# CPU_Logic.net
KiCad netlist of a schematic drawn in Altium Designer
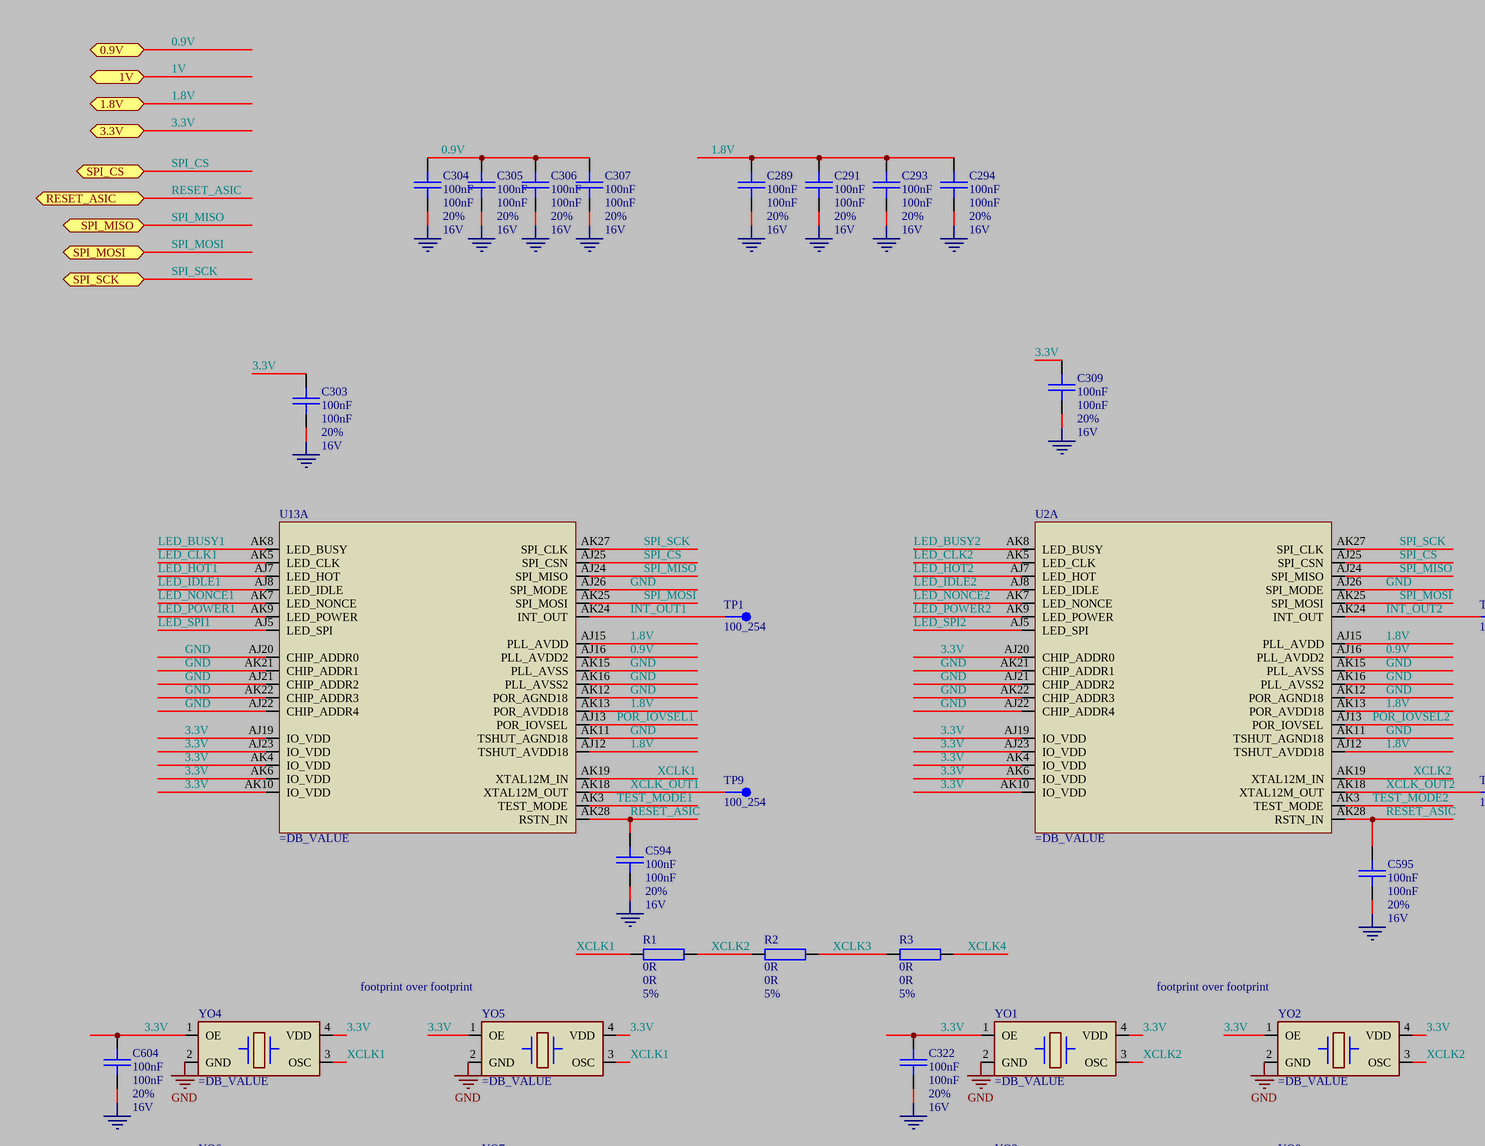
[diagram p0: CPU_Logic.SchDoc, top left]
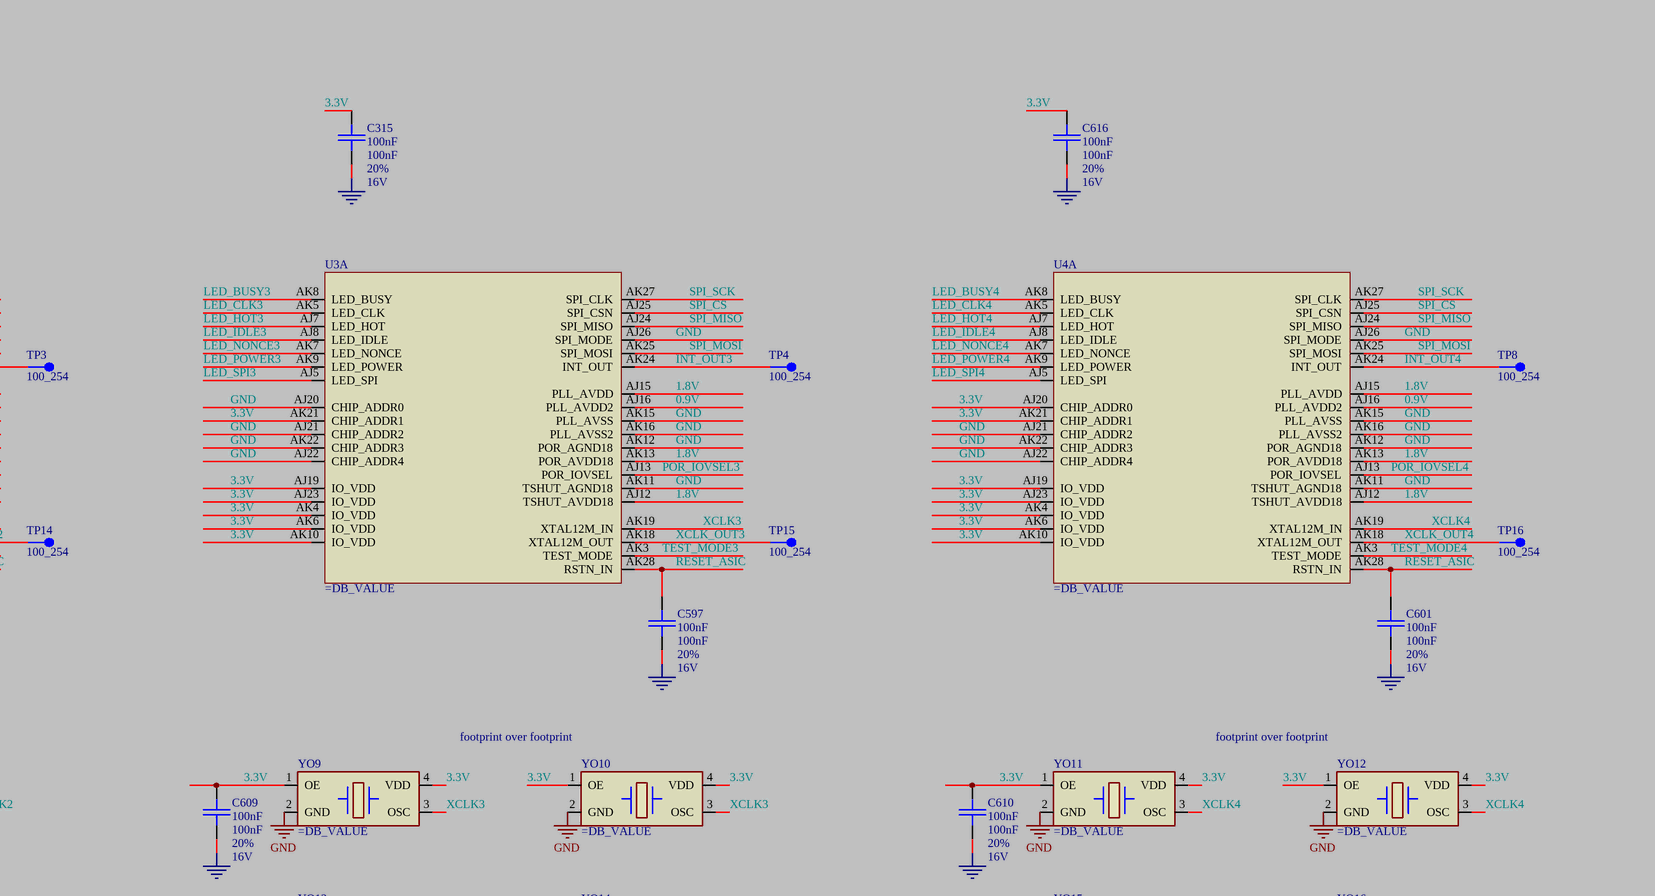
[diagram p1: CPU_Logic.SchDoc, top right]
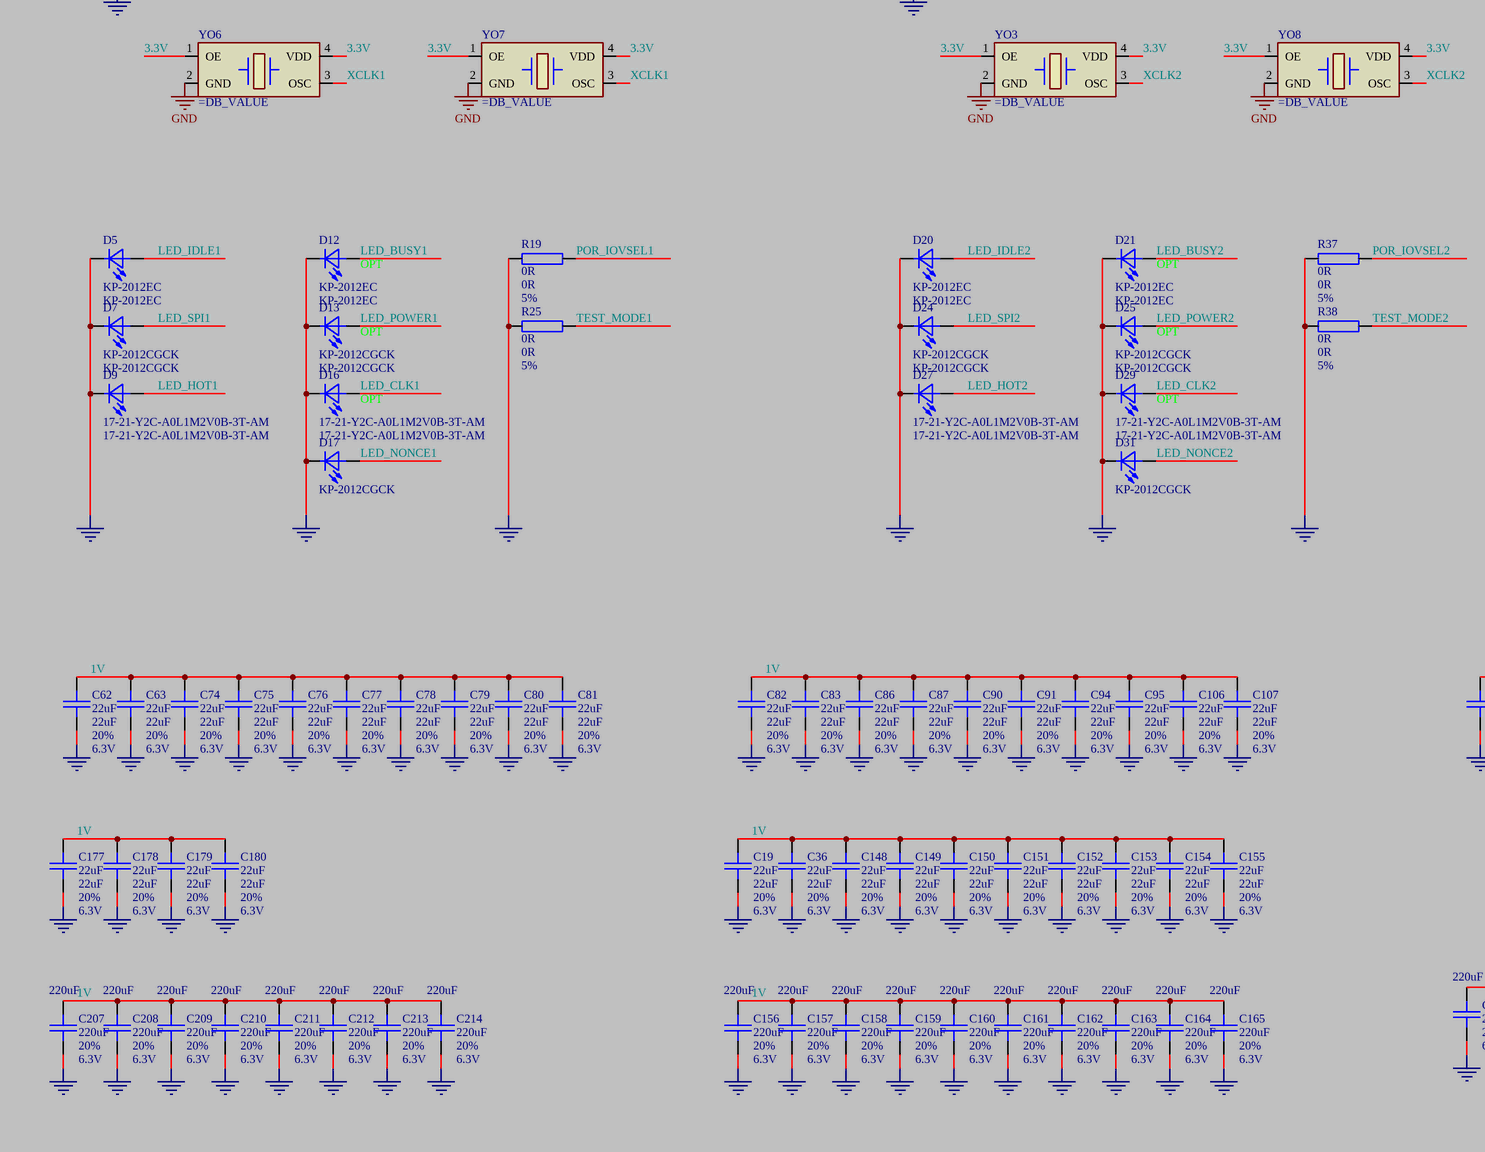
[diagram p2: CPU_Logic.SchDoc, bottom left]
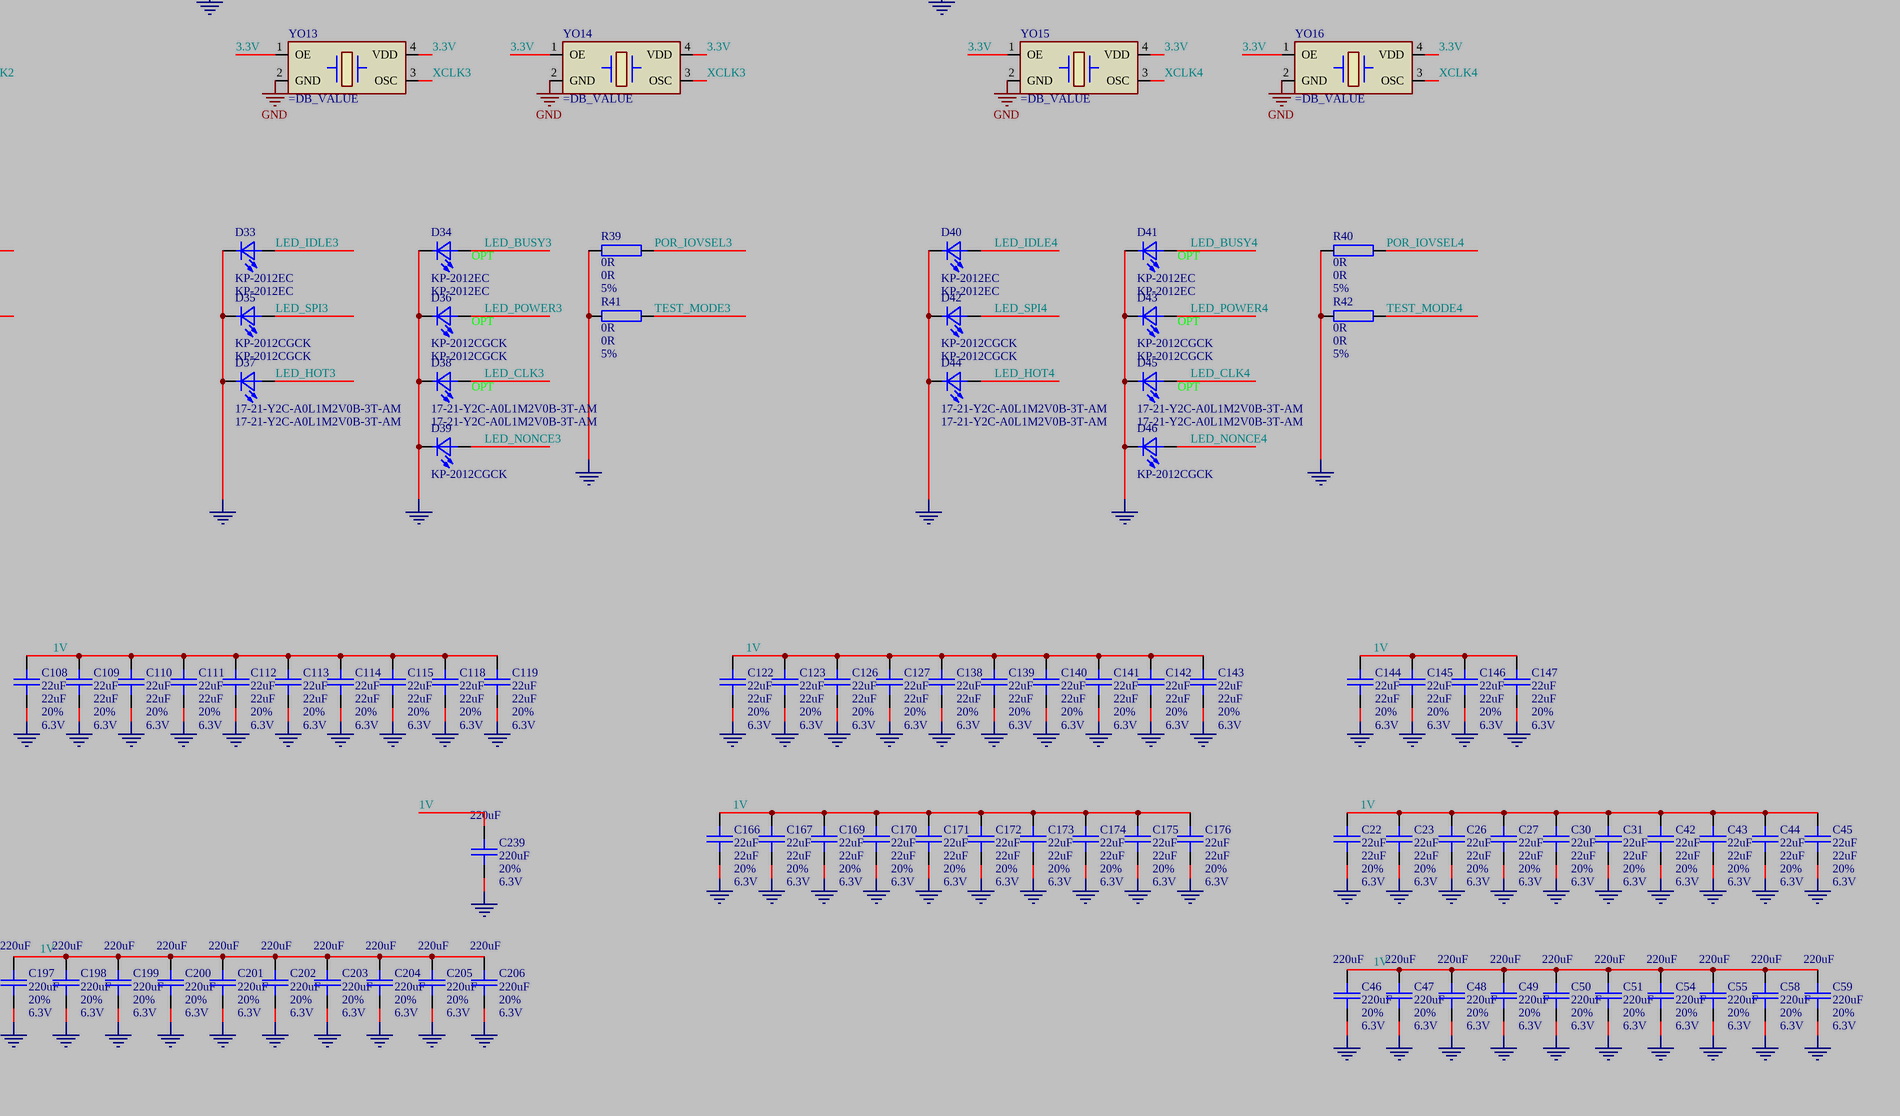
[diagram p3: CPU_Logic.SchDoc, bottom right]

(export (version "E")
  (design (tool "Eeschema 10.0.6"))
  (components
    (comp (ref "C19")
      (value "22uF")
      (footprint "SMD_0805_CAPC2012X145N")
      (fields
        (field (name "DB_PART_NUMBER") "CAP000043686")
        (field (name "DB_VALUE") "22uF")
        (field (name "DB_TOLERANCE") "20%")
        (field (name "DB_VOLTAGE") "6.3V")
        (field (name "DB_MANUFACTURER_PART") "KEMET    C0805C226M9PAC")
        (field (name "DB_APPROVED_BY") "ISHIDDEN=T")
      )
      (libsource (lib "Database_Libs1") (part "C"))
    )
    (comp (ref "C22")
      (value "22uF")
      (footprint "SMD_0805_CAPC2012X145N")
      (fields
        (field (name "DB_PART_NUMBER") "CAP000043686")
        (field (name "DB_VALUE") "22uF")
        (field (name "DB_TOLERANCE") "20%")
        (field (name "DB_VOLTAGE") "6.3V")
        (field (name "DB_MANUFACTURER_PART") "KEMET    C0805C226M9PAC")
        (field (name "DB_APPROVED_BY") "ISHIDDEN=T")
      )
      (libsource (lib "Database_Libs1") (part "C"))
    )
    (comp (ref "C23")
      (value "22uF")
      (footprint "SMD_0805_CAPC2012X145N")
      (fields
        (field (name "DB_PART_NUMBER") "CAP000043686")
        (field (name "DB_VALUE") "22uF")
        (field (name "DB_TOLERANCE") "20%")
        (field (name "DB_VOLTAGE") "6.3V")
        (field (name "DB_MANUFACTURER_PART") "KEMET    C0805C226M9PAC")
        (field (name "DB_APPROVED_BY") "ISHIDDEN=T")
      )
      (libsource (lib "Database_Libs1") (part "C"))
    )
    (comp (ref "C26")
      (value "22uF")
      (footprint "SMD_0805_CAPC2012X145N")
      (fields
        (field (name "DB_PART_NUMBER") "CAP000043686")
        (field (name "DB_VALUE") "22uF")
        (field (name "DB_TOLERANCE") "20%")
        (field (name "DB_VOLTAGE") "6.3V")
        (field (name "DB_MANUFACTURER_PART") "KEMET    C0805C226M9PAC")
        (field (name "DB_APPROVED_BY") "ISHIDDEN=T")
      )
      (libsource (lib "Database_Libs1") (part "C"))
    )
    (comp (ref "C27")
      (value "22uF")
      (footprint "SMD_0805_CAPC2012X145N")
      (fields
        (field (name "DB_PART_NUMBER") "CAP000043686")
        (field (name "DB_VALUE") "22uF")
        (field (name "DB_TOLERANCE") "20%")
        (field (name "DB_VOLTAGE") "6.3V")
        (field (name "DB_MANUFACTURER_PART") "KEMET    C0805C226M9PAC")
        (field (name "DB_APPROVED_BY") "ISHIDDEN=T")
      )
      (libsource (lib "Database_Libs1") (part "C"))
    )
    (comp (ref "C30")
      (value "22uF")
      (footprint "SMD_0805_CAPC2012X145N")
      (fields
        (field (name "DB_PART_NUMBER") "CAP000043686")
        (field (name "DB_VALUE") "22uF")
        (field (name "DB_TOLERANCE") "20%")
        (field (name "DB_VOLTAGE") "6.3V")
        (field (name "DB_MANUFACTURER_PART") "KEMET    C0805C226M9PAC")
        (field (name "DB_APPROVED_BY") "ISHIDDEN=T")
      )
      (libsource (lib "Database_Libs1") (part "C"))
    )
    (comp (ref "C31")
      (value "22uF")
      (footprint "SMD_0805_CAPC2012X145N")
      (fields
        (field (name "DB_PART_NUMBER") "CAP000043686")
        (field (name "DB_VALUE") "22uF")
        (field (name "DB_TOLERANCE") "20%")
        (field (name "DB_VOLTAGE") "6.3V")
        (field (name "DB_MANUFACTURER_PART") "KEMET    C0805C226M9PAC")
        (field (name "DB_APPROVED_BY") "ISHIDDEN=T")
      )
      (libsource (lib "Database_Libs1") (part "C"))
    )
    (comp (ref "C36")
      (value "22uF")
      (footprint "SMD_0805_CAPC2012X145N")
      (fields
        (field (name "DB_PART_NUMBER") "CAP000043686")
        (field (name "DB_VALUE") "22uF")
        (field (name "DB_TOLERANCE") "20%")
        (field (name "DB_VOLTAGE") "6.3V")
        (field (name "DB_MANUFACTURER_PART") "KEMET    C0805C226M9PAC")
        (field (name "DB_APPROVED_BY") "ISHIDDEN=T")
      )
      (libsource (lib "Database_Libs1") (part "C"))
    )
    (comp (ref "C42")
      (value "22uF")
      (footprint "SMD_0805_CAPC2012X145N")
      (fields
        (field (name "DB_PART_NUMBER") "CAP000043686")
        (field (name "DB_VALUE") "22uF")
        (field (name "DB_TOLERANCE") "20%")
        (field (name "DB_VOLTAGE") "6.3V")
        (field (name "DB_MANUFACTURER_PART") "KEMET    C0805C226M9PAC")
        (field (name "DB_APPROVED_BY") "ISHIDDEN=T")
      )
      (libsource (lib "Database_Libs1") (part "C"))
    )
    (comp (ref "C43")
      (value "22uF")
      (footprint "SMD_0805_CAPC2012X145N")
      (fields
        (field (name "DB_PART_NUMBER") "CAP000043686")
        (field (name "DB_VALUE") "22uF")
        (field (name "DB_TOLERANCE") "20%")
        (field (name "DB_VOLTAGE") "6.3V")
        (field (name "DB_MANUFACTURER_PART") "KEMET    C0805C226M9PAC")
        (field (name "DB_APPROVED_BY") "ISHIDDEN=T")
      )
      (libsource (lib "Database_Libs1") (part "C"))
    )
    (comp (ref "C44")
      (value "22uF")
      (footprint "SMD_0805_CAPC2012X145N")
      (fields
        (field (name "DB_PART_NUMBER") "CAP000043686")
        (field (name "DB_VALUE") "22uF")
        (field (name "DB_TOLERANCE") "20%")
        (field (name "DB_VOLTAGE") "6.3V")
        (field (name "DB_MANUFACTURER_PART") "KEMET    C0805C226M9PAC")
        (field (name "DB_APPROVED_BY") "ISHIDDEN=T")
      )
      (libsource (lib "Database_Libs1") (part "C"))
    )
    (comp (ref "C45")
      (value "22uF")
      (footprint "SMD_0805_CAPC2012X145N")
      (fields
        (field (name "DB_PART_NUMBER") "CAP000043686")
        (field (name "DB_VALUE") "22uF")
        (field (name "DB_TOLERANCE") "20%")
        (field (name "DB_VOLTAGE") "6.3V")
        (field (name "DB_MANUFACTURER_PART") "KEMET    C0805C226M9PAC")
        (field (name "DB_APPROVED_BY") "ISHIDDEN=T")
      )
      (libsource (lib "Database_Libs1") (part "C"))
    )
    (comp (ref "C46")
      (value "220uF")
      (footprint "SMD_1210_CAPC3225X279N")
      (fields
        (field (name "DB_PART_NUMBER") "CAP000047355")
        (field (name "DB_VALUE") "220uF")
        (field (name "DB_TOLERANCE") "20%")
        (field (name "DB_VOLTAGE") "6.3V")
        (field (name "DB_MANUFACTURER_PART") "SAMSUNG    CL32A227MQVNNNE")
        (field (name "DB_APPROVED_BY") "VSN")
      )
      (libsource (lib "Database_Libs1") (part "C"))
    )
    (comp (ref "C47")
      (value "220uF")
      (footprint "SMD_1210_CAPC3225X279N")
      (fields
        (field (name "DB_PART_NUMBER") "CAP000047355")
        (field (name "DB_VALUE") "220uF")
        (field (name "DB_TOLERANCE") "20%")
        (field (name "DB_VOLTAGE") "6.3V")
        (field (name "DB_MANUFACTURER_PART") "SAMSUNG    CL32A227MQVNNNE")
        (field (name "DB_APPROVED_BY") "VSN")
      )
      (libsource (lib "Database_Libs1") (part "C"))
    )
    (comp (ref "C48")
      (value "220uF")
      (footprint "SMD_1210_CAPC3225X279N")
      (fields
        (field (name "DB_PART_NUMBER") "CAP000047355")
        (field (name "DB_VALUE") "220uF")
        (field (name "DB_TOLERANCE") "20%")
        (field (name "DB_VOLTAGE") "6.3V")
        (field (name "DB_MANUFACTURER_PART") "SAMSUNG    CL32A227MQVNNNE")
        (field (name "DB_APPROVED_BY") "VSN")
      )
      (libsource (lib "Database_Libs1") (part "C"))
    )
    (comp (ref "C49")
      (value "220uF")
      (footprint "SMD_1210_CAPC3225X279N")
      (fields
        (field (name "DB_PART_NUMBER") "CAP000047355")
        (field (name "DB_VALUE") "220uF")
        (field (name "DB_TOLERANCE") "20%")
        (field (name "DB_VOLTAGE") "6.3V")
        (field (name "DB_MANUFACTURER_PART") "SAMSUNG    CL32A227MQVNNNE")
        (field (name "DB_APPROVED_BY") "VSN")
      )
      (libsource (lib "Database_Libs1") (part "C"))
    )
    (comp (ref "C50")
      (value "220uF")
      (footprint "SMD_1210_CAPC3225X279N")
      (fields
        (field (name "DB_PART_NUMBER") "CAP000047355")
        (field (name "DB_VALUE") "220uF")
        (field (name "DB_TOLERANCE") "20%")
        (field (name "DB_VOLTAGE") "6.3V")
        (field (name "DB_MANUFACTURER_PART") "SAMSUNG    CL32A227MQVNNNE")
        (field (name "DB_APPROVED_BY") "VSN")
      )
      (libsource (lib "Database_Libs1") (part "C"))
    )
    (comp (ref "C51")
      (value "220uF")
      (footprint "SMD_1210_CAPC3225X279N")
      (fields
        (field (name "DB_PART_NUMBER") "CAP000047355")
        (field (name "DB_VALUE") "220uF")
        (field (name "DB_TOLERANCE") "20%")
        (field (name "DB_VOLTAGE") "6.3V")
        (field (name "DB_MANUFACTURER_PART") "SAMSUNG    CL32A227MQVNNNE")
        (field (name "DB_APPROVED_BY") "VSN")
      )
      (libsource (lib "Database_Libs1") (part "C"))
    )
    (comp (ref "C54")
      (value "220uF")
      (footprint "SMD_1210_CAPC3225X279N")
      (fields
        (field (name "DB_PART_NUMBER") "CAP000047355")
        (field (name "DB_VALUE") "220uF")
        (field (name "DB_TOLERANCE") "20%")
        (field (name "DB_VOLTAGE") "6.3V")
        (field (name "DB_MANUFACTURER_PART") "SAMSUNG    CL32A227MQVNNNE")
        (field (name "DB_APPROVED_BY") "VSN")
      )
      (libsource (lib "Database_Libs1") (part "C"))
    )
    (comp (ref "C55")
      (value "220uF")
      (footprint "SMD_1210_CAPC3225X279N")
      (fields
        (field (name "DB_PART_NUMBER") "CAP000047355")
        (field (name "DB_VALUE") "220uF")
        (field (name "DB_TOLERANCE") "20%")
        (field (name "DB_VOLTAGE") "6.3V")
        (field (name "DB_MANUFACTURER_PART") "SAMSUNG    CL32A227MQVNNNE")
        (field (name "DB_APPROVED_BY") "VSN")
      )
      (libsource (lib "Database_Libs1") (part "C"))
    )
    (comp (ref "C58")
      (value "220uF")
      (footprint "SMD_1210_CAPC3225X279N")
      (fields
        (field (name "DB_PART_NUMBER") "CAP000047355")
        (field (name "DB_VALUE") "220uF")
        (field (name "DB_TOLERANCE") "20%")
        (field (name "DB_VOLTAGE") "6.3V")
        (field (name "DB_MANUFACTURER_PART") "SAMSUNG    CL32A227MQVNNNE")
        (field (name "DB_APPROVED_BY") "VSN")
      )
      (libsource (lib "Database_Libs1") (part "C"))
    )
    (comp (ref "C59")
      (value "220uF")
      (footprint "SMD_1210_CAPC3225X279N")
      (fields
        (field (name "DB_PART_NUMBER") "CAP000047355")
        (field (name "DB_VALUE") "220uF")
        (field (name "DB_TOLERANCE") "20%")
        (field (name "DB_VOLTAGE") "6.3V")
        (field (name "DB_MANUFACTURER_PART") "SAMSUNG    CL32A227MQVNNNE")
        (field (name "DB_APPROVED_BY") "VSN")
      )
      (libsource (lib "Database_Libs1") (part "C"))
    )
    (comp (ref "C62")
      (value "22uF")
      (footprint "SMD_0805_CAPC2012X145N")
      (fields
        (field (name "DB_PART_NUMBER") "CAP000043686")
        (field (name "DB_VALUE") "22uF")
        (field (name "DB_TOLERANCE") "20%")
        (field (name "DB_VOLTAGE") "6.3V")
        (field (name "DB_MANUFACTURER_PART") "KEMET    C0805C226M9PAC")
        (field (name "DB_APPROVED_BY") "ISHIDDEN=T")
      )
      (libsource (lib "Database_Libs1") (part "C"))
    )
    (comp (ref "C63")
      (value "22uF")
      (footprint "SMD_0805_CAPC2012X145N")
      (fields
        (field (name "DB_PART_NUMBER") "CAP000043686")
        (field (name "DB_VALUE") "22uF")
        (field (name "DB_TOLERANCE") "20%")
        (field (name "DB_VOLTAGE") "6.3V")
        (field (name "DB_MANUFACTURER_PART") "KEMET    C0805C226M9PAC")
        (field (name "DB_APPROVED_BY") "ISHIDDEN=T")
      )
      (libsource (lib "Database_Libs1") (part "C"))
    )
    (comp (ref "C74")
      (value "22uF")
      (footprint "SMD_0805_CAPC2012X145N")
      (fields
        (field (name "DB_PART_NUMBER") "CAP000043686")
        (field (name "DB_VALUE") "22uF")
        (field (name "DB_TOLERANCE") "20%")
        (field (name "DB_VOLTAGE") "6.3V")
        (field (name "DB_MANUFACTURER_PART") "KEMET    C0805C226M9PAC")
        (field (name "DB_APPROVED_BY") "ISHIDDEN=T")
      )
      (libsource (lib "Database_Libs1") (part "C"))
    )
    (comp (ref "C75")
      (value "22uF")
      (footprint "SMD_0805_CAPC2012X145N")
      (fields
        (field (name "DB_PART_NUMBER") "CAP000043686")
        (field (name "DB_VALUE") "22uF")
        (field (name "DB_TOLERANCE") "20%")
        (field (name "DB_VOLTAGE") "6.3V")
        (field (name "DB_MANUFACTURER_PART") "KEMET    C0805C226M9PAC")
        (field (name "DB_APPROVED_BY") "ISHIDDEN=T")
      )
      (libsource (lib "Database_Libs1") (part "C"))
    )
    (comp (ref "C76")
      (value "22uF")
      (footprint "SMD_0805_CAPC2012X145N")
      (fields
        (field (name "DB_PART_NUMBER") "CAP000043686")
        (field (name "DB_VALUE") "22uF")
        (field (name "DB_TOLERANCE") "20%")
        (field (name "DB_VOLTAGE") "6.3V")
        (field (name "DB_MANUFACTURER_PART") "KEMET    C0805C226M9PAC")
        (field (name "DB_APPROVED_BY") "ISHIDDEN=T")
      )
      (libsource (lib "Database_Libs1") (part "C"))
    )
    (comp (ref "C77")
      (value "22uF")
      (footprint "SMD_0805_CAPC2012X145N")
      (fields
        (field (name "DB_PART_NUMBER") "CAP000043686")
        (field (name "DB_VALUE") "22uF")
        (field (name "DB_TOLERANCE") "20%")
        (field (name "DB_VOLTAGE") "6.3V")
        (field (name "DB_MANUFACTURER_PART") "KEMET    C0805C226M9PAC")
        (field (name "DB_APPROVED_BY") "ISHIDDEN=T")
      )
      (libsource (lib "Database_Libs1") (part "C"))
    )
    (comp (ref "C78")
      (value "22uF")
      (footprint "SMD_0805_CAPC2012X145N")
      (fields
        (field (name "DB_PART_NUMBER") "CAP000043686")
        (field (name "DB_VALUE") "22uF")
        (field (name "DB_TOLERANCE") "20%")
        (field (name "DB_VOLTAGE") "6.3V")
        (field (name "DB_MANUFACTURER_PART") "KEMET    C0805C226M9PAC")
        (field (name "DB_APPROVED_BY") "ISHIDDEN=T")
      )
      (libsource (lib "Database_Libs1") (part "C"))
    )
    (comp (ref "C79")
      (value "22uF")
      (footprint "SMD_0805_CAPC2012X145N")
      (fields
        (field (name "DB_PART_NUMBER") "CAP000043686")
        (field (name "DB_VALUE") "22uF")
        (field (name "DB_TOLERANCE") "20%")
        (field (name "DB_VOLTAGE") "6.3V")
        (field (name "DB_MANUFACTURER_PART") "KEMET    C0805C226M9PAC")
        (field (name "DB_APPROVED_BY") "ISHIDDEN=T")
      )
      (libsource (lib "Database_Libs1") (part "C"))
    )
    (comp (ref "C80")
      (value "22uF")
      (footprint "SMD_0805_CAPC2012X145N")
      (fields
        (field (name "DB_PART_NUMBER") "CAP000043686")
        (field (name "DB_VALUE") "22uF")
        (field (name "DB_TOLERANCE") "20%")
        (field (name "DB_VOLTAGE") "6.3V")
        (field (name "DB_MANUFACTURER_PART") "KEMET    C0805C226M9PAC")
        (field (name "DB_APPROVED_BY") "ISHIDDEN=T")
      )
      (libsource (lib "Database_Libs1") (part "C"))
    )
    (comp (ref "C81")
      (value "22uF")
      (footprint "SMD_0805_CAPC2012X145N")
      (fields
        (field (name "DB_PART_NUMBER") "CAP000043686")
        (field (name "DB_VALUE") "22uF")
        (field (name "DB_TOLERANCE") "20%")
        (field (name "DB_VOLTAGE") "6.3V")
        (field (name "DB_MANUFACTURER_PART") "KEMET    C0805C226M9PAC")
        (field (name "DB_APPROVED_BY") "ISHIDDEN=T")
      )
      (libsource (lib "Database_Libs1") (part "C"))
    )
    (comp (ref "C82")
      (value "22uF")
      (footprint "SMD_0805_CAPC2012X145N")
      (fields
        (field (name "DB_PART_NUMBER") "CAP000043686")
        (field (name "DB_VALUE") "22uF")
        (field (name "DB_TOLERANCE") "20%")
        (field (name "DB_VOLTAGE") "6.3V")
        (field (name "DB_MANUFACTURER_PART") "KEMET    C0805C226M9PAC")
        (field (name "DB_APPROVED_BY") "ISHIDDEN=T")
      )
      (libsource (lib "Database_Libs1") (part "C"))
    )
    (comp (ref "C83")
      (value "22uF")
      (footprint "SMD_0805_CAPC2012X145N")
      (fields
        (field (name "DB_PART_NUMBER") "CAP000043686")
        (field (name "DB_VALUE") "22uF")
        (field (name "DB_TOLERANCE") "20%")
        (field (name "DB_VOLTAGE") "6.3V")
        (field (name "DB_MANUFACTURER_PART") "KEMET    C0805C226M9PAC")
        (field (name "DB_APPROVED_BY") "ISHIDDEN=T")
      )
      (libsource (lib "Database_Libs1") (part "C"))
    )
    (comp (ref "C86")
      (value "22uF")
      (footprint "SMD_0805_CAPC2012X145N")
      (fields
        (field (name "DB_PART_NUMBER") "CAP000043686")
        (field (name "DB_VALUE") "22uF")
        (field (name "DB_TOLERANCE") "20%")
        (field (name "DB_VOLTAGE") "6.3V")
        (field (name "DB_MANUFACTURER_PART") "KEMET    C0805C226M9PAC")
        (field (name "DB_APPROVED_BY") "ISHIDDEN=T")
      )
      (libsource (lib "Database_Libs1") (part "C"))
    )
    (comp (ref "C87")
      (value "22uF")
      (footprint "SMD_0805_CAPC2012X145N")
      (fields
        (field (name "DB_PART_NUMBER") "CAP000043686")
        (field (name "DB_VALUE") "22uF")
        (field (name "DB_TOLERANCE") "20%")
        (field (name "DB_VOLTAGE") "6.3V")
        (field (name "DB_MANUFACTURER_PART") "KEMET    C0805C226M9PAC")
        (field (name "DB_APPROVED_BY") "ISHIDDEN=T")
      )
      (libsource (lib "Database_Libs1") (part "C"))
    )
    (comp (ref "C90")
      (value "22uF")
      (footprint "SMD_0805_CAPC2012X145N")
      (fields
        (field (name "DB_PART_NUMBER") "CAP000043686")
        (field (name "DB_VALUE") "22uF")
        (field (name "DB_TOLERANCE") "20%")
        (field (name "DB_VOLTAGE") "6.3V")
        (field (name "DB_MANUFACTURER_PART") "KEMET    C0805C226M9PAC")
        (field (name "DB_APPROVED_BY") "ISHIDDEN=T")
      )
      (libsource (lib "Database_Libs1") (part "C"))
    )
    (comp (ref "C91")
      (value "22uF")
      (footprint "SMD_0805_CAPC2012X145N")
      (fields
        (field (name "DB_PART_NUMBER") "CAP000043686")
        (field (name "DB_VALUE") "22uF")
        (field (name "DB_TOLERANCE") "20%")
        (field (name "DB_VOLTAGE") "6.3V")
        (field (name "DB_MANUFACTURER_PART") "KEMET    C0805C226M9PAC")
        (field (name "DB_APPROVED_BY") "ISHIDDEN=T")
      )
      (libsource (lib "Database_Libs1") (part "C"))
    )
    (comp (ref "C94")
      (value "22uF")
      (footprint "SMD_0805_CAPC2012X145N")
      (fields
        (field (name "DB_PART_NUMBER") "CAP000043686")
        (field (name "DB_VALUE") "22uF")
        (field (name "DB_TOLERANCE") "20%")
        (field (name "DB_VOLTAGE") "6.3V")
        (field (name "DB_MANUFACTURER_PART") "KEMET    C0805C226M9PAC")
        (field (name "DB_APPROVED_BY") "ISHIDDEN=T")
      )
      (libsource (lib "Database_Libs1") (part "C"))
    )
    (comp (ref "C95")
      (value "22uF")
      (footprint "SMD_0805_CAPC2012X145N")
      (fields
        (field (name "DB_PART_NUMBER") "CAP000043686")
        (field (name "DB_VALUE") "22uF")
        (field (name "DB_TOLERANCE") "20%")
        (field (name "DB_VOLTAGE") "6.3V")
        (field (name "DB_MANUFACTURER_PART") "KEMET    C0805C226M9PAC")
        (field (name "DB_APPROVED_BY") "ISHIDDEN=T")
      )
      (libsource (lib "Database_Libs1") (part "C"))
    )
    (comp (ref "C106")
      (value "22uF")
      (footprint "SMD_0805_CAPC2012X145N")
      (fields
        (field (name "DB_PART_NUMBER") "CAP000043686")
        (field (name "DB_VALUE") "22uF")
        (field (name "DB_TOLERANCE") "20%")
        (field (name "DB_VOLTAGE") "6.3V")
        (field (name "DB_MANUFACTURER_PART") "KEMET    C0805C226M9PAC")
        (field (name "DB_APPROVED_BY") "ISHIDDEN=T")
      )
      (libsource (lib "Database_Libs1") (part "C"))
    )
    (comp (ref "C107")
      (value "22uF")
      (footprint "SMD_0805_CAPC2012X145N")
      (fields
        (field (name "DB_PART_NUMBER") "CAP000043686")
        (field (name "DB_VALUE") "22uF")
        (field (name "DB_TOLERANCE") "20%")
        (field (name "DB_VOLTAGE") "6.3V")
        (field (name "DB_MANUFACTURER_PART") "KEMET    C0805C226M9PAC")
        (field (name "DB_APPROVED_BY") "ISHIDDEN=T")
      )
      (libsource (lib "Database_Libs1") (part "C"))
    )
    (comp (ref "C108")
      (value "22uF")
      (footprint "SMD_0805_CAPC2012X145N")
      (fields
        (field (name "DB_PART_NUMBER") "CAP000043686")
        (field (name "DB_VALUE") "22uF")
        (field (name "DB_TOLERANCE") "20%")
        (field (name "DB_VOLTAGE") "6.3V")
        (field (name "DB_MANUFACTURER_PART") "KEMET    C0805C226M9PAC")
        (field (name "DB_APPROVED_BY") "ISHIDDEN=T")
      )
      (libsource (lib "Database_Libs1") (part "C"))
    )
    (comp (ref "C109")
      (value "22uF")
      (footprint "SMD_0805_CAPC2012X145N")
      (fields
        (field (name "DB_PART_NUMBER") "CAP000043686")
        (field (name "DB_VALUE") "22uF")
        (field (name "DB_TOLERANCE") "20%")
        (field (name "DB_VOLTAGE") "6.3V")
        (field (name "DB_MANUFACTURER_PART") "KEMET    C0805C226M9PAC")
        (field (name "DB_APPROVED_BY") "ISHIDDEN=T")
      )
      (libsource (lib "Database_Libs1") (part "C"))
    )
    (comp (ref "C110")
      (value "22uF")
      (footprint "SMD_0805_CAPC2012X145N")
      (fields
        (field (name "DB_PART_NUMBER") "CAP000043686")
        (field (name "DB_VALUE") "22uF")
        (field (name "DB_TOLERANCE") "20%")
        (field (name "DB_VOLTAGE") "6.3V")
        (field (name "DB_MANUFACTURER_PART") "KEMET    C0805C226M9PAC")
        (field (name "DB_APPROVED_BY") "ISHIDDEN=T")
      )
      (libsource (lib "Database_Libs1") (part "C"))
    )
    (comp (ref "C111")
      (value "22uF")
      (footprint "SMD_0805_CAPC2012X145N")
      (fields
        (field (name "DB_PART_NUMBER") "CAP000043686")
        (field (name "DB_VALUE") "22uF")
        (field (name "DB_TOLERANCE") "20%")
        (field (name "DB_VOLTAGE") "6.3V")
        (field (name "DB_MANUFACTURER_PART") "KEMET    C0805C226M9PAC")
        (field (name "DB_APPROVED_BY") "ISHIDDEN=T")
      )
      (libsource (lib "Database_Libs1") (part "C"))
    )
    (comp (ref "C112")
      (value "22uF")
      (footprint "SMD_0805_CAPC2012X145N")
      (fields
        (field (name "DB_PART_NUMBER") "CAP000043686")
        (field (name "DB_VALUE") "22uF")
        (field (name "DB_TOLERANCE") "20%")
        (field (name "DB_VOLTAGE") "6.3V")
        (field (name "DB_MANUFACTURER_PART") "KEMET    C0805C226M9PAC")
        (field (name "DB_APPROVED_BY") "ISHIDDEN=T")
      )
      (libsource (lib "Database_Libs1") (part "C"))
    )
    (comp (ref "C113")
      (value "22uF")
      (footprint "SMD_0805_CAPC2012X145N")
      (fields
        (field (name "DB_PART_NUMBER") "CAP000043686")
        (field (name "DB_VALUE") "22uF")
        (field (name "DB_TOLERANCE") "20%")
        (field (name "DB_VOLTAGE") "6.3V")
        (field (name "DB_MANUFACTURER_PART") "KEMET    C0805C226M9PAC")
        (field (name "DB_APPROVED_BY") "ISHIDDEN=T")
      )
      (libsource (lib "Database_Libs1") (part "C"))
    )
    (comp (ref "C114")
      (value "22uF")
      (footprint "SMD_0805_CAPC2012X145N")
      (fields
        (field (name "DB_PART_NUMBER") "CAP000043686")
        (field (name "DB_VALUE") "22uF")
        (field (name "DB_TOLERANCE") "20%")
        (field (name "DB_VOLTAGE") "6.3V")
        (field (name "DB_MANUFACTURER_PART") "KEMET    C0805C226M9PAC")
        (field (name "DB_APPROVED_BY") "ISHIDDEN=T")
      )
      (libsource (lib "Database_Libs1") (part "C"))
    )
    (comp (ref "C115")
      (value "22uF")
      (footprint "SMD_0805_CAPC2012X145N")
      (fields
        (field (name "DB_PART_NUMBER") "CAP000043686")
        (field (name "DB_VALUE") "22uF")
        (field (name "DB_TOLERANCE") "20%")
        (field (name "DB_VOLTAGE") "6.3V")
        (field (name "DB_MANUFACTURER_PART") "KEMET    C0805C226M9PAC")
        (field (name "DB_APPROVED_BY") "ISHIDDEN=T")
      )
      (libsource (lib "Database_Libs1") (part "C"))
    )
    (comp (ref "C118")
      (value "22uF")
      (footprint "SMD_0805_CAPC2012X145N")
      (fields
        (field (name "DB_PART_NUMBER") "CAP000043686")
        (field (name "DB_VALUE") "22uF")
        (field (name "DB_TOLERANCE") "20%")
        (field (name "DB_VOLTAGE") "6.3V")
        (field (name "DB_MANUFACTURER_PART") "KEMET    C0805C226M9PAC")
        (field (name "DB_APPROVED_BY") "ISHIDDEN=T")
      )
      (libsource (lib "Database_Libs1") (part "C"))
    )
    (comp (ref "C119")
      (value "22uF")
      (footprint "SMD_0805_CAPC2012X145N")
      (fields
        (field (name "DB_PART_NUMBER") "CAP000043686")
        (field (name "DB_VALUE") "22uF")
        (field (name "DB_TOLERANCE") "20%")
        (field (name "DB_VOLTAGE") "6.3V")
        (field (name "DB_MANUFACTURER_PART") "KEMET    C0805C226M9PAC")
        (field (name "DB_APPROVED_BY") "ISHIDDEN=T")
      )
      (libsource (lib "Database_Libs1") (part "C"))
    )
    (comp (ref "C122")
      (value "22uF")
      (footprint "SMD_0805_CAPC2012X145N")
      (fields
        (field (name "DB_PART_NUMBER") "CAP000043686")
        (field (name "DB_VALUE") "22uF")
        (field (name "DB_TOLERANCE") "20%")
        (field (name "DB_VOLTAGE") "6.3V")
        (field (name "DB_MANUFACTURER_PART") "KEMET    C0805C226M9PAC")
        (field (name "DB_APPROVED_BY") "ISHIDDEN=T")
      )
      (libsource (lib "Database_Libs1") (part "C"))
    )
    (comp (ref "C123")
      (value "22uF")
      (footprint "SMD_0805_CAPC2012X145N")
      (fields
        (field (name "DB_PART_NUMBER") "CAP000043686")
        (field (name "DB_VALUE") "22uF")
        (field (name "DB_TOLERANCE") "20%")
        (field (name "DB_VOLTAGE") "6.3V")
        (field (name "DB_MANUFACTURER_PART") "KEMET    C0805C226M9PAC")
        (field (name "DB_APPROVED_BY") "ISHIDDEN=T")
      )
      (libsource (lib "Database_Libs1") (part "C"))
    )
    (comp (ref "C126")
      (value "22uF")
      (footprint "SMD_0805_CAPC2012X145N")
      (fields
        (field (name "DB_PART_NUMBER") "CAP000043686")
        (field (name "DB_VALUE") "22uF")
        (field (name "DB_TOLERANCE") "20%")
        (field (name "DB_VOLTAGE") "6.3V")
        (field (name "DB_MANUFACTURER_PART") "KEMET    C0805C226M9PAC")
        (field (name "DB_APPROVED_BY") "ISHIDDEN=T")
      )
      (libsource (lib "Database_Libs1") (part "C"))
    )
    (comp (ref "C127")
      (value "22uF")
      (footprint "SMD_0805_CAPC2012X145N")
      (fields
        (field (name "DB_PART_NUMBER") "CAP000043686")
        (field (name "DB_VALUE") "22uF")
        (field (name "DB_TOLERANCE") "20%")
        (field (name "DB_VOLTAGE") "6.3V")
        (field (name "DB_MANUFACTURER_PART") "KEMET    C0805C226M9PAC")
        (field (name "DB_APPROVED_BY") "ISHIDDEN=T")
      )
      (libsource (lib "Database_Libs1") (part "C"))
    )
    (comp (ref "C138")
      (value "22uF")
      (footprint "SMD_0805_CAPC2012X145N")
      (fields
        (field (name "DB_PART_NUMBER") "CAP000043686")
        (field (name "DB_VALUE") "22uF")
        (field (name "DB_TOLERANCE") "20%")
        (field (name "DB_VOLTAGE") "6.3V")
        (field (name "DB_MANUFACTURER_PART") "KEMET    C0805C226M9PAC")
        (field (name "DB_APPROVED_BY") "ISHIDDEN=T")
      )
      (libsource (lib "Database_Libs1") (part "C"))
    )
    (comp (ref "C139")
      (value "22uF")
      (footprint "SMD_0805_CAPC2012X145N")
      (fields
        (field (name "DB_PART_NUMBER") "CAP000043686")
        (field (name "DB_VALUE") "22uF")
        (field (name "DB_TOLERANCE") "20%")
        (field (name "DB_VOLTAGE") "6.3V")
        (field (name "DB_MANUFACTURER_PART") "KEMET    C0805C226M9PAC")
        (field (name "DB_APPROVED_BY") "ISHIDDEN=T")
      )
      (libsource (lib "Database_Libs1") (part "C"))
    )
    (comp (ref "C140")
      (value "22uF")
      (footprint "SMD_0805_CAPC2012X145N")
      (fields
        (field (name "DB_PART_NUMBER") "CAP000043686")
        (field (name "DB_VALUE") "22uF")
        (field (name "DB_TOLERANCE") "20%")
        (field (name "DB_VOLTAGE") "6.3V")
        (field (name "DB_MANUFACTURER_PART") "KEMET    C0805C226M9PAC")
        (field (name "DB_APPROVED_BY") "ISHIDDEN=T")
      )
      (libsource (lib "Database_Libs1") (part "C"))
    )
    (comp (ref "C141")
      (value "22uF")
      (footprint "SMD_0805_CAPC2012X145N")
      (fields
        (field (name "DB_PART_NUMBER") "CAP000043686")
        (field (name "DB_VALUE") "22uF")
        (field (name "DB_TOLERANCE") "20%")
        (field (name "DB_VOLTAGE") "6.3V")
        (field (name "DB_MANUFACTURER_PART") "KEMET    C0805C226M9PAC")
        (field (name "DB_APPROVED_BY") "ISHIDDEN=T")
      )
      (libsource (lib "Database_Libs1") (part "C"))
    )
    (comp (ref "C142")
      (value "22uF")
      (footprint "SMD_0805_CAPC2012X145N")
      (fields
        (field (name "DB_PART_NUMBER") "CAP000043686")
        (field (name "DB_VALUE") "22uF")
        (field (name "DB_TOLERANCE") "20%")
        (field (name "DB_VOLTAGE") "6.3V")
        (field (name "DB_MANUFACTURER_PART") "KEMET    C0805C226M9PAC")
        (field (name "DB_APPROVED_BY") "ISHIDDEN=T")
      )
      (libsource (lib "Database_Libs1") (part "C"))
    )
    (comp (ref "C143")
      (value "22uF")
      (footprint "SMD_0805_CAPC2012X145N")
      (fields
        (field (name "DB_PART_NUMBER") "CAP000043686")
        (field (name "DB_VALUE") "22uF")
        (field (name "DB_TOLERANCE") "20%")
        (field (name "DB_VOLTAGE") "6.3V")
        (field (name "DB_MANUFACTURER_PART") "KEMET    C0805C226M9PAC")
        (field (name "DB_APPROVED_BY") "ISHIDDEN=T")
      )
      (libsource (lib "Database_Libs1") (part "C"))
    )
    (comp (ref "C144")
      (value "22uF")
      (footprint "SMD_0805_CAPC2012X145N")
      (fields
        (field (name "DB_PART_NUMBER") "CAP000043686")
        (field (name "DB_VALUE") "22uF")
        (field (name "DB_TOLERANCE") "20%")
        (field (name "DB_VOLTAGE") "6.3V")
        (field (name "DB_MANUFACTURER_PART") "KEMET    C0805C226M9PAC")
        (field (name "DB_APPROVED_BY") "ISHIDDEN=T")
      )
      (libsource (lib "Database_Libs1") (part "C"))
    )
    (comp (ref "C145")
      (value "22uF")
      (footprint "SMD_0805_CAPC2012X145N")
      (fields
        (field (name "DB_PART_NUMBER") "CAP000043686")
        (field (name "DB_VALUE") "22uF")
        (field (name "DB_TOLERANCE") "20%")
        (field (name "DB_VOLTAGE") "6.3V")
        (field (name "DB_MANUFACTURER_PART") "KEMET    C0805C226M9PAC")
        (field (name "DB_APPROVED_BY") "ISHIDDEN=T")
      )
      (libsource (lib "Database_Libs1") (part "C"))
    )
    (comp (ref "C146")
      (value "22uF")
      (footprint "SMD_0805_CAPC2012X145N")
      (fields
        (field (name "DB_PART_NUMBER") "CAP000043686")
        (field (name "DB_VALUE") "22uF")
        (field (name "DB_TOLERANCE") "20%")
        (field (name "DB_VOLTAGE") "6.3V")
        (field (name "DB_MANUFACTURER_PART") "KEMET    C0805C226M9PAC")
        (field (name "DB_APPROVED_BY") "ISHIDDEN=T")
      )
      (libsource (lib "Database_Libs1") (part "C"))
    )
    (comp (ref "C147")
      (value "22uF")
      (footprint "SMD_0805_CAPC2012X145N")
      (fields
        (field (name "DB_PART_NUMBER") "CAP000043686")
        (field (name "DB_VALUE") "22uF")
        (field (name "DB_TOLERANCE") "20%")
        (field (name "DB_VOLTAGE") "6.3V")
        (field (name "DB_MANUFACTURER_PART") "KEMET    C0805C226M9PAC")
        (field (name "DB_APPROVED_BY") "ISHIDDEN=T")
      )
      (libsource (lib "Database_Libs1") (part "C"))
    )
    (comp (ref "C148")
      (value "22uF")
      (footprint "SMD_0805_CAPC2012X145N")
      (fields
        (field (name "DB_PART_NUMBER") "CAP000043686")
        (field (name "DB_VALUE") "22uF")
        (field (name "DB_TOLERANCE") "20%")
        (field (name "DB_VOLTAGE") "6.3V")
        (field (name "DB_MANUFACTURER_PART") "KEMET    C0805C226M9PAC")
        (field (name "DB_APPROVED_BY") "ISHIDDEN=T")
      )
      (libsource (lib "Database_Libs1") (part "C"))
    )
    (comp (ref "C149")
      (value "22uF")
      (footprint "SMD_0805_CAPC2012X145N")
      (fields
        (field (name "DB_PART_NUMBER") "CAP000043686")
        (field (name "DB_VALUE") "22uF")
        (field (name "DB_TOLERANCE") "20%")
        (field (name "DB_VOLTAGE") "6.3V")
        (field (name "DB_MANUFACTURER_PART") "KEMET    C0805C226M9PAC")
        (field (name "DB_APPROVED_BY") "ISHIDDEN=T")
      )
      (libsource (lib "Database_Libs1") (part "C"))
    )
    (comp (ref "C150")
      (value "22uF")
      (footprint "SMD_0805_CAPC2012X145N")
      (fields
        (field (name "DB_PART_NUMBER") "CAP000043686")
        (field (name "DB_VALUE") "22uF")
        (field (name "DB_TOLERANCE") "20%")
        (field (name "DB_VOLTAGE") "6.3V")
        (field (name "DB_MANUFACTURER_PART") "KEMET    C0805C226M9PAC")
        (field (name "DB_APPROVED_BY") "ISHIDDEN=T")
      )
      (libsource (lib "Database_Libs1") (part "C"))
    )
    (comp (ref "C151")
      (value "22uF")
      (footprint "SMD_0805_CAPC2012X145N")
      (fields
        (field (name "DB_PART_NUMBER") "CAP000043686")
        (field (name "DB_VALUE") "22uF")
        (field (name "DB_TOLERANCE") "20%")
        (field (name "DB_VOLTAGE") "6.3V")
        (field (name "DB_MANUFACTURER_PART") "KEMET    C0805C226M9PAC")
        (field (name "DB_APPROVED_BY") "ISHIDDEN=T")
      )
      (libsource (lib "Database_Libs1") (part "C"))
    )
    (comp (ref "C152")
      (value "22uF")
      (footprint "SMD_0805_CAPC2012X145N")
      (fields
        (field (name "DB_PART_NUMBER") "CAP000043686")
        (field (name "DB_VALUE") "22uF")
        (field (name "DB_TOLERANCE") "20%")
        (field (name "DB_VOLTAGE") "6.3V")
        (field (name "DB_MANUFACTURER_PART") "KEMET    C0805C226M9PAC")
        (field (name "DB_APPROVED_BY") "ISHIDDEN=T")
      )
      (libsource (lib "Database_Libs1") (part "C"))
    )
    (comp (ref "C153")
      (value "22uF")
      (footprint "SMD_0805_CAPC2012X145N")
      (fields
        (field (name "DB_PART_NUMBER") "CAP000043686")
        (field (name "DB_VALUE") "22uF")
        (field (name "DB_TOLERANCE") "20%")
        (field (name "DB_VOLTAGE") "6.3V")
        (field (name "DB_MANUFACTURER_PART") "KEMET    C0805C226M9PAC")
        (field (name "DB_APPROVED_BY") "ISHIDDEN=T")
      )
      (libsource (lib "Database_Libs1") (part "C"))
    )
    (comp (ref "C154")
      (value "22uF")
      (footprint "SMD_0805_CAPC2012X145N")
      (fields
        (field (name "DB_PART_NUMBER") "CAP000043686")
        (field (name "DB_VALUE") "22uF")
        (field (name "DB_TOLERANCE") "20%")
        (field (name "DB_VOLTAGE") "6.3V")
        (field (name "DB_MANUFACTURER_PART") "KEMET    C0805C226M9PAC")
        (field (name "DB_APPROVED_BY") "ISHIDDEN=T")
      )
      (libsource (lib "Database_Libs1") (part "C"))
    )
    (comp (ref "C155")
      (value "22uF")
      (footprint "SMD_0805_CAPC2012X145N")
      (fields
        (field (name "DB_PART_NUMBER") "CAP000043686")
        (field (name "DB_VALUE") "22uF")
        (field (name "DB_TOLERANCE") "20%")
        (field (name "DB_VOLTAGE") "6.3V")
        (field (name "DB_MANUFACTURER_PART") "KEMET    C0805C226M9PAC")
        (field (name "DB_APPROVED_BY") "ISHIDDEN=T")
      )
      (libsource (lib "Database_Libs1") (part "C"))
    )
    (comp (ref "C156")
      (value "220uF")
      (footprint "SMD_1210_CAPC3225X279N")
      (fields
        (field (name "DB_PART_NUMBER") "CAP000047355")
        (field (name "DB_VALUE") "220uF")
        (field (name "DB_TOLERANCE") "20%")
        (field (name "DB_VOLTAGE") "6.3V")
        (field (name "DB_MANUFACTURER_PART") "SAMSUNG    CL32A227MQVNNNE")
        (field (name "DB_APPROVED_BY") "VSN")
      )
      (libsource (lib "Database_Libs1") (part "C"))
    )
    (comp (ref "C157")
      (value "220uF")
      (footprint "SMD_1210_CAPC3225X279N")
      (fields
        (field (name "DB_PART_NUMBER") "CAP000047355")
        (field (name "DB_VALUE") "220uF")
        (field (name "DB_TOLERANCE") "20%")
        (field (name "DB_VOLTAGE") "6.3V")
        (field (name "DB_MANUFACTURER_PART") "SAMSUNG    CL32A227MQVNNNE")
        (field (name "DB_APPROVED_BY") "VSN")
      )
      (libsource (lib "Database_Libs1") (part "C"))
    )
    (comp (ref "C158")
      (value "220uF")
      (footprint "SMD_1210_CAPC3225X279N")
      (fields
        (field (name "DB_PART_NUMBER") "CAP000047355")
        (field (name "DB_VALUE") "220uF")
        (field (name "DB_TOLERANCE") "20%")
        (field (name "DB_VOLTAGE") "6.3V")
        (field (name "DB_MANUFACTURER_PART") "SAMSUNG    CL32A227MQVNNNE")
        (field (name "DB_APPROVED_BY") "VSN")
      )
      (libsource (lib "Database_Libs1") (part "C"))
    )
    (comp (ref "C159")
      (value "220uF")
      (footprint "SMD_1210_CAPC3225X279N")
      (fields
        (field (name "DB_PART_NUMBER") "CAP000047355")
        (field (name "DB_VALUE") "220uF")
        (field (name "DB_TOLERANCE") "20%")
        (field (name "DB_VOLTAGE") "6.3V")
        (field (name "DB_MANUFACTURER_PART") "SAMSUNG    CL32A227MQVNNNE")
        (field (name "DB_APPROVED_BY") "VSN")
      )
      (libsource (lib "Database_Libs1") (part "C"))
    )
    (comp (ref "C160")
      (value "220uF")
      (footprint "SMD_1210_CAPC3225X279N")
      (fields
        (field (name "DB_PART_NUMBER") "CAP000047355")
        (field (name "DB_VALUE") "220uF")
        (field (name "DB_TOLERANCE") "20%")
        (field (name "DB_VOLTAGE") "6.3V")
        (field (name "DB_MANUFACTURER_PART") "SAMSUNG    CL32A227MQVNNNE")
        (field (name "DB_APPROVED_BY") "VSN")
      )
      (libsource (lib "Database_Libs1") (part "C"))
    )
    (comp (ref "C161")
      (value "220uF")
      (footprint "SMD_1210_CAPC3225X279N")
      (fields
        (field (name "DB_PART_NUMBER") "CAP000047355")
        (field (name "DB_VALUE") "220uF")
        (field (name "DB_TOLERANCE") "20%")
        (field (name "DB_VOLTAGE") "6.3V")
        (field (name "DB_MANUFACTURER_PART") "SAMSUNG    CL32A227MQVNNNE")
        (field (name "DB_APPROVED_BY") "VSN")
      )
      (libsource (lib "Database_Libs1") (part "C"))
    )
    (comp (ref "C162")
      (value "220uF")
      (footprint "SMD_1210_CAPC3225X279N")
      (fields
        (field (name "DB_PART_NUMBER") "CAP000047355")
        (field (name "DB_VALUE") "220uF")
        (field (name "DB_TOLERANCE") "20%")
        (field (name "DB_VOLTAGE") "6.3V")
        (field (name "DB_MANUFACTURER_PART") "SAMSUNG    CL32A227MQVNNNE")
        (field (name "DB_APPROVED_BY") "VSN")
      )
      (libsource (lib "Database_Libs1") (part "C"))
    )
    (comp (ref "C163")
      (value "220uF")
      (footprint "SMD_1210_CAPC3225X279N")
      (fields
        (field (name "DB_PART_NUMBER") "CAP000047355")
        (field (name "DB_VALUE") "220uF")
        (field (name "DB_TOLERANCE") "20%")
        (field (name "DB_VOLTAGE") "6.3V")
        (field (name "DB_MANUFACTURER_PART") "SAMSUNG    CL32A227MQVNNNE")
        (field (name "DB_APPROVED_BY") "VSN")
      )
      (libsource (lib "Database_Libs1") (part "C"))
    )
    (comp (ref "C164")
      (value "220uF")
      (footprint "SMD_1210_CAPC3225X279N")
      (fields
        (field (name "DB_PART_NUMBER") "CAP000047355")
        (field (name "DB_VALUE") "220uF")
        (field (name "DB_TOLERANCE") "20%")
        (field (name "DB_VOLTAGE") "6.3V")
        (field (name "DB_MANUFACTURER_PART") "SAMSUNG    CL32A227MQVNNNE")
        (field (name "DB_APPROVED_BY") "VSN")
      )
      (libsource (lib "Database_Libs1") (part "C"))
    )
    (comp (ref "C165")
      (value "220uF")
      (footprint "SMD_1210_CAPC3225X279N")
      (fields
        (field (name "DB_PART_NUMBER") "CAP000047355")
        (field (name "DB_VALUE") "220uF")
        (field (name "DB_TOLERANCE") "20%")
        (field (name "DB_VOLTAGE") "6.3V")
        (field (name "DB_MANUFACTURER_PART") "SAMSUNG    CL32A227MQVNNNE")
        (field (name "DB_APPROVED_BY") "VSN")
      )
      (libsource (lib "Database_Libs1") (part "C"))
    )
    (comp (ref "C166")
      (value "22uF")
      (footprint "SMD_0805_CAPC2012X145N")
      (fields
        (field (name "DB_PART_NUMBER") "CAP000043686")
        (field (name "DB_VALUE") "22uF")
        (field (name "DB_TOLERANCE") "20%")
        (field (name "DB_VOLTAGE") "6.3V")
        (field (name "DB_MANUFACTURER_PART") "KEMET    C0805C226M9PAC")
        (field (name "DB_APPROVED_BY") "ISHIDDEN=T")
      )
      (libsource (lib "Database_Libs1") (part "C"))
    )
    (comp (ref "C167")
      (value "22uF")
      (footprint "SMD_0805_CAPC2012X145N")
      (fields
        (field (name "DB_PART_NUMBER") "CAP000043686")
        (field (name "DB_VALUE") "22uF")
        (field (name "DB_TOLERANCE") "20%")
        (field (name "DB_VOLTAGE") "6.3V")
        (field (name "DB_MANUFACTURER_PART") "KEMET    C0805C226M9PAC")
        (field (name "DB_APPROVED_BY") "ISHIDDEN=T")
      )
      (libsource (lib "Database_Libs1") (part "C"))
    )
    (comp (ref "C169")
      (value "22uF")
      (footprint "SMD_0805_CAPC2012X145N")
      (fields
        (field (name "DB_PART_NUMBER") "CAP000043686")
        (field (name "DB_VALUE") "22uF")
        (field (name "DB_TOLERANCE") "20%")
        (field (name "DB_VOLTAGE") "6.3V")
        (field (name "DB_MANUFACTURER_PART") "KEMET    C0805C226M9PAC")
        (field (name "DB_APPROVED_BY") "ISHIDDEN=T")
      )
      (libsource (lib "Database_Libs1") (part "C"))
    )
    (comp (ref "C170")
      (value "22uF")
      (footprint "SMD_0805_CAPC2012X145N")
      (fields
        (field (name "DB_PART_NUMBER") "CAP000043686")
        (field (name "DB_VALUE") "22uF")
        (field (name "DB_TOLERANCE") "20%")
        (field (name "DB_VOLTAGE") "6.3V")
        (field (name "DB_MANUFACTURER_PART") "KEMET    C0805C226M9PAC")
        (field (name "DB_APPROVED_BY") "ISHIDDEN=T")
      )
      (libsource (lib "Database_Libs1") (part "C"))
    )
    (comp (ref "C171")
      (value "22uF")
      (footprint "SMD_0805_CAPC2012X145N")
      (fields
        (field (name "DB_PART_NUMBER") "CAP000043686")
        (field (name "DB_VALUE") "22uF")
        (field (name "DB_TOLERANCE") "20%")
        (field (name "DB_VOLTAGE") "6.3V")
        (field (name "DB_MANUFACTURER_PART") "KEMET    C0805C226M9PAC")
        (field (name "DB_APPROVED_BY") "ISHIDDEN=T")
      )
      (libsource (lib "Database_Libs1") (part "C"))
    )
    (comp (ref "C172")
      (value "22uF")
      (footprint "SMD_0805_CAPC2012X145N")
      (fields
        (field (name "DB_PART_NUMBER") "CAP000043686")
        (field (name "DB_VALUE") "22uF")
        (field (name "DB_TOLERANCE") "20%")
        (field (name "DB_VOLTAGE") "6.3V")
        (field (name "DB_MANUFACTURER_PART") "KEMET    C0805C226M9PAC")
        (field (name "DB_APPROVED_BY") "ISHIDDEN=T")
      )
      (libsource (lib "Database_Libs1") (part "C"))
    )
    (comp (ref "C173")
      (value "22uF")
      (footprint "SMD_0805_CAPC2012X145N")
      (fields
        (field (name "DB_PART_NUMBER") "CAP000043686")
        (field (name "DB_VALUE") "22uF")
        (field (name "DB_TOLERANCE") "20%")
        (field (name "DB_VOLTAGE") "6.3V")
        (field (name "DB_MANUFACTURER_PART") "KEMET    C0805C226M9PAC")
        (field (name "DB_APPROVED_BY") "ISHIDDEN=T")
      )
      (libsource (lib "Database_Libs1") (part "C"))
    )
    (comp (ref "C174")
      (value "22uF")
      (footprint "SMD_0805_CAPC2012X145N")
      (fields
        (field (name "DB_PART_NUMBER") "CAP000043686")
        (field (name "DB_VALUE") "22uF")
        (field (name "DB_TOLERANCE") "20%")
        (field (name "DB_VOLTAGE") "6.3V")
        (field (name "DB_MANUFACTURER_PART") "KEMET    C0805C226M9PAC")
        (field (name "DB_APPROVED_BY") "ISHIDDEN=T")
      )
      (libsource (lib "Database_Libs1") (part "C"))
    )
    (comp (ref "C175")
      (value "22uF")
      (footprint "SMD_0805_CAPC2012X145N")
      (fields
        (field (name "DB_PART_NUMBER") "CAP000043686")
        (field (name "DB_VALUE") "22uF")
        (field (name "DB_TOLERANCE") "20%")
        (field (name "DB_VOLTAGE") "6.3V")
        (field (name "DB_MANUFACTURER_PART") "KEMET    C0805C226M9PAC")
        (field (name "DB_APPROVED_BY") "ISHIDDEN=T")
      )
      (libsource (lib "Database_Libs1") (part "C"))
    )
    (comp (ref "C176")
      (value "22uF")
      (footprint "SMD_0805_CAPC2012X145N")
      (fields
        (field (name "DB_PART_NUMBER") "CAP000043686")
        (field (name "DB_VALUE") "22uF")
        (field (name "DB_TOLERANCE") "20%")
        (field (name "DB_VOLTAGE") "6.3V")
        (field (name "DB_MANUFACTURER_PART") "KEMET    C0805C226M9PAC")
        (field (name "DB_APPROVED_BY") "ISHIDDEN=T")
      )
      (libsource (lib "Database_Libs1") (part "C"))
    )
    (comp (ref "C177")
      (value "22uF")
      (footprint "SMD_0805_CAPC2012X145N")
      (fields
        (field (name "DB_PART_NUMBER") "CAP000043686")
        (field (name "DB_VALUE") "22uF")
        (field (name "DB_TOLERANCE") "20%")
        (field (name "DB_VOLTAGE") "6.3V")
        (field (name "DB_MANUFACTURER_PART") "KEMET    C0805C226M9PAC")
        (field (name "DB_APPROVED_BY") "ISHIDDEN=T")
      )
      (libsource (lib "Database_Libs1") (part "C"))
    )
    (comp (ref "C178")
      (value "22uF")
      (footprint "SMD_0805_CAPC2012X145N")
      (fields
        (field (name "DB_PART_NUMBER") "CAP000043686")
        (field (name "DB_VALUE") "22uF")
        (field (name "DB_TOLERANCE") "20%")
        (field (name "DB_VOLTAGE") "6.3V")
        (field (name "DB_MANUFACTURER_PART") "KEMET    C0805C226M9PAC")
        (field (name "DB_APPROVED_BY") "ISHIDDEN=T")
      )
      (libsource (lib "Database_Libs1") (part "C"))
    )
    (comp (ref "C179")
      (value "22uF")
      (footprint "SMD_0805_CAPC2012X145N")
      (fields
        (field (name "DB_PART_NUMBER") "CAP000043686")
        (field (name "DB_VALUE") "22uF")
        (field (name "DB_TOLERANCE") "20%")
        (field (name "DB_VOLTAGE") "6.3V")
        (field (name "DB_MANUFACTURER_PART") "KEMET    C0805C226M9PAC")
        (field (name "DB_APPROVED_BY") "ISHIDDEN=T")
      )
      (libsource (lib "Database_Libs1") (part "C"))
    )
    (comp (ref "C180")
      (value "22uF")
      (footprint "SMD_0805_CAPC2012X145N")
      (fields
        (field (name "DB_PART_NUMBER") "CAP000043686")
        (field (name "DB_VALUE") "22uF")
        (field (name "DB_TOLERANCE") "20%")
        (field (name "DB_VOLTAGE") "6.3V")
        (field (name "DB_MANUFACTURER_PART") "KEMET    C0805C226M9PAC")
        (field (name "DB_APPROVED_BY") "ISHIDDEN=T")
      )
      (libsource (lib "Database_Libs1") (part "C"))
    )
    (comp (ref "C197")
      (value "220uF")
      (footprint "SMD_1210_CAPC3225X279N")
      (fields
        (field (name "DB_PART_NUMBER") "CAP000047355")
        (field (name "DB_VALUE") "220uF")
        (field (name "DB_TOLERANCE") "20%")
        (field (name "DB_VOLTAGE") "6.3V")
        (field (name "DB_MANUFACTURER_PART") "SAMSUNG    CL32A227MQVNNNE")
        (field (name "DB_APPROVED_BY") "VSN")
      )
      (libsource (lib "Database_Libs1") (part "C"))
    )
    (comp (ref "C198")
      (value "220uF")
      (footprint "SMD_1210_CAPC3225X279N")
      (fields
        (field (name "DB_PART_NUMBER") "CAP000047355")
        (field (name "DB_VALUE") "220uF")
        (field (name "DB_TOLERANCE") "20%")
        (field (name "DB_VOLTAGE") "6.3V")
        (field (name "DB_MANUFACTURER_PART") "SAMSUNG    CL32A227MQVNNNE")
        (field (name "DB_APPROVED_BY") "VSN")
      )
      (libsource (lib "Database_Libs1") (part "C"))
    )
    (comp (ref "C199")
      (value "220uF")
      (footprint "SMD_1210_CAPC3225X279N")
      (fields
        (field (name "DB_PART_NUMBER") "CAP000047355")
        (field (name "DB_VALUE") "220uF")
        (field (name "DB_TOLERANCE") "20%")
        (field (name "DB_VOLTAGE") "6.3V")
        (field (name "DB_MANUFACTURER_PART") "SAMSUNG    CL32A227MQVNNNE")
        (field (name "DB_APPROVED_BY") "VSN")
      )
      (libsource (lib "Database_Libs1") (part "C"))
    )
    (comp (ref "C200")
      (value "220uF")
      (footprint "SMD_1210_CAPC3225X279N")
      (fields
        (field (name "DB_PART_NUMBER") "CAP000047355")
        (field (name "DB_VALUE") "220uF")
        (field (name "DB_TOLERANCE") "20%")
        (field (name "DB_VOLTAGE") "6.3V")
        (field (name "DB_MANUFACTURER_PART") "SAMSUNG    CL32A227MQVNNNE")
        (field (name "DB_APPROVED_BY") "VSN")
      )
      (libsource (lib "Database_Libs1") (part "C"))
    )
    (comp (ref "C201")
      (value "220uF")
      (footprint "SMD_1210_CAPC3225X279N")
      (fields
        (field (name "DB_PART_NUMBER") "CAP000047355")
        (field (name "DB_VALUE") "220uF")
        (field (name "DB_TOLERANCE") "20%")
        (field (name "DB_VOLTAGE") "6.3V")
        (field (name "DB_MANUFACTURER_PART") "SAMSUNG    CL32A227MQVNNNE")
        (field (name "DB_APPROVED_BY") "VSN")
      )
      (libsource (lib "Database_Libs1") (part "C"))
    )
    (comp (ref "C202")
      (value "220uF")
      (footprint "SMD_1210_CAPC3225X279N")
      (fields
        (field (name "DB_PART_NUMBER") "CAP000047355")
        (field (name "DB_VALUE") "220uF")
        (field (name "DB_TOLERANCE") "20%")
        (field (name "DB_VOLTAGE") "6.3V")
        (field (name "DB_MANUFACTURER_PART") "SAMSUNG    CL32A227MQVNNNE")
        (field (name "DB_APPROVED_BY") "VSN")
      )
      (libsource (lib "Database_Libs1") (part "C"))
    )
    (comp (ref "C203")
      (value "220uF")
      (footprint "SMD_1210_CAPC3225X279N")
      (fields
        (field (name "DB_PART_NUMBER") "CAP000047355")
        (field (name "DB_VALUE") "220uF")
        (field (name "DB_TOLERANCE") "20%")
        (field (name "DB_VOLTAGE") "6.3V")
        (field (name "DB_MANUFACTURER_PART") "SAMSUNG    CL32A227MQVNNNE")
        (field (name "DB_APPROVED_BY") "VSN")
      )
      (libsource (lib "Database_Libs1") (part "C"))
    )
    (comp (ref "C204")
      (value "220uF")
      (footprint "SMD_1210_CAPC3225X279N")
      (fields
        (field (name "DB_PART_NUMBER") "CAP000047355")
        (field (name "DB_VALUE") "220uF")
        (field (name "DB_TOLERANCE") "20%")
        (field (name "DB_VOLTAGE") "6.3V")
        (field (name "DB_MANUFACTURER_PART") "SAMSUNG    CL32A227MQVNNNE")
        (field (name "DB_APPROVED_BY") "VSN")
      )
      (libsource (lib "Database_Libs1") (part "C"))
    )
    (comp (ref "C205")
      (value "220uF")
      (footprint "SMD_1210_CAPC3225X279N")
      (fields
        (field (name "DB_PART_NUMBER") "CAP000047355")
        (field (name "DB_VALUE") "220uF")
        (field (name "DB_TOLERANCE") "20%")
        (field (name "DB_VOLTAGE") "6.3V")
        (field (name "DB_MANUFACTURER_PART") "SAMSUNG    CL32A227MQVNNNE")
        (field (name "DB_APPROVED_BY") "VSN")
      )
      (libsource (lib "Database_Libs1") (part "C"))
    )
    (comp (ref "C206")
      (value "220uF")
      (footprint "SMD_1210_CAPC3225X279N")
      (fields
        (field (name "DB_PART_NUMBER") "CAP000047355")
        (field (name "DB_VALUE") "220uF")
        (field (name "DB_TOLERANCE") "20%")
        (field (name "DB_VOLTAGE") "6.3V")
        (field (name "DB_MANUFACTURER_PART") "SAMSUNG    CL32A227MQVNNNE")
        (field (name "DB_APPROVED_BY") "VSN")
      )
      (libsource (lib "Database_Libs1") (part "C"))
    )
    (comp (ref "C207")
      (value "220uF")
      (footprint "SMD_1210_CAPC3225X279N")
      (fields
        (field (name "DB_PART_NUMBER") "CAP000047355")
        (field (name "DB_VALUE") "220uF")
        (field (name "DB_TOLERANCE") "20%")
        (field (name "DB_VOLTAGE") "6.3V")
        (field (name "DB_MANUFACTURER_PART") "SAMSUNG    CL32A227MQVNNNE")
        (field (name "DB_APPROVED_BY") "VSN")
      )
      (libsource (lib "Database_Libs1") (part "C"))
    )
    (comp (ref "C208")
      (value "220uF")
      (footprint "SMD_1210_CAPC3225X279N")
      (fields
        (field (name "DB_PART_NUMBER") "CAP000047355")
        (field (name "DB_VALUE") "220uF")
        (field (name "DB_TOLERANCE") "20%")
        (field (name "DB_VOLTAGE") "6.3V")
        (field (name "DB_MANUFACTURER_PART") "SAMSUNG    CL32A227MQVNNNE")
        (field (name "DB_APPROVED_BY") "VSN")
      )
      (libsource (lib "Database_Libs1") (part "C"))
    )
    (comp (ref "C209")
      (value "220uF")
      (footprint "SMD_1210_CAPC3225X279N")
      (fields
        (field (name "DB_PART_NUMBER") "CAP000047355")
        (field (name "DB_VALUE") "220uF")
        (field (name "DB_TOLERANCE") "20%")
        (field (name "DB_VOLTAGE") "6.3V")
        (field (name "DB_MANUFACTURER_PART") "SAMSUNG    CL32A227MQVNNNE")
        (field (name "DB_APPROVED_BY") "VSN")
      )
      (libsource (lib "Database_Libs1") (part "C"))
    )
    (comp (ref "C210")
      (value "220uF")
      (footprint "SMD_1210_CAPC3225X279N")
      (fields
        (field (name "DB_PART_NUMBER") "CAP000047355")
        (field (name "DB_VALUE") "220uF")
        (field (name "DB_TOLERANCE") "20%")
        (field (name "DB_VOLTAGE") "6.3V")
        (field (name "DB_MANUFACTURER_PART") "SAMSUNG    CL32A227MQVNNNE")
        (field (name "DB_APPROVED_BY") "VSN")
      )
      (libsource (lib "Database_Libs1") (part "C"))
    )
    (comp (ref "C211")
      (value "220uF")
      (footprint "SMD_1210_CAPC3225X279N")
      (fields
        (field (name "DB_PART_NUMBER") "CAP000047355")
        (field (name "DB_VALUE") "220uF")
        (field (name "DB_TOLERANCE") "20%")
        (field (name "DB_VOLTAGE") "6.3V")
        (field (name "DB_MANUFACTURER_PART") "SAMSUNG    CL32A227MQVNNNE")
        (field (name "DB_APPROVED_BY") "VSN")
      )
      (libsource (lib "Database_Libs1") (part "C"))
    )
    (comp (ref "C212")
      (value "220uF")
      (footprint "SMD_1210_CAPC3225X279N")
      (fields
        (field (name "DB_PART_NUMBER") "CAP000047355")
        (field (name "DB_VALUE") "220uF")
        (field (name "DB_TOLERANCE") "20%")
        (field (name "DB_VOLTAGE") "6.3V")
        (field (name "DB_MANUFACTURER_PART") "SAMSUNG    CL32A227MQVNNNE")
        (field (name "DB_APPROVED_BY") "VSN")
      )
      (libsource (lib "Database_Libs1") (part "C"))
    )
    (comp (ref "C213")
      (value "220uF")
      (footprint "SMD_1210_CAPC3225X279N")
      (fields
        (field (name "DB_PART_NUMBER") "CAP000047355")
        (field (name "DB_VALUE") "220uF")
        (field (name "DB_TOLERANCE") "20%")
        (field (name "DB_VOLTAGE") "6.3V")
        (field (name "DB_MANUFACTURER_PART") "SAMSUNG    CL32A227MQVNNNE")
        (field (name "DB_APPROVED_BY") "VSN")
      )
      (libsource (lib "Database_Libs1") (part "C"))
    )
    (comp (ref "C214")
      (value "220uF")
      (footprint "SMD_1210_CAPC3225X279N")
      (fields
        (field (name "DB_PART_NUMBER") "CAP000047355")
        (field (name "DB_VALUE") "220uF")
        (field (name "DB_TOLERANCE") "20%")
        (field (name "DB_VOLTAGE") "6.3V")
        (field (name "DB_MANUFACTURER_PART") "SAMSUNG    CL32A227MQVNNNE")
        (field (name "DB_APPROVED_BY") "VSN")
      )
      (libsource (lib "Database_Libs1") (part "C"))
    )
    (comp (ref "C239")
      (value "220uF")
      (footprint "SMD_1210_CAPC3225X279N")
      (fields
        (field (name "DB_PART_NUMBER") "CAP000047355")
        (field (name "DB_VALUE") "220uF")
        (field (name "DB_TOLERANCE") "20%")
        (field (name "DB_VOLTAGE") "6.3V")
        (field (name "DB_MANUFACTURER_PART") "SAMSUNG    CL32A227MQVNNNE")
        (field (name "DB_APPROVED_BY") "VSN")
      )
      (libsource (lib "Database_Libs1") (part "C"))
    )
    (comp (ref "C289")
      (value "100nF")
      (footprint "SMD_0603_CAPC1608X95N")
      (fields
        (field (name "DB_PART_NUMBER") "CAP000027236")
        (field (name "DB_VALUE") "100nF")
        (field (name "DB_TOLERANCE") "20%")
        (field (name "DB_VOLTAGE") "16V")
        (field (name "DB_MANUFACTURER_PART") "KEMET    C0603C104M4RAC")
        (field (name "DB_APPROVED_BY") "ISHIDDEN=T")
      )
      (libsource (lib "Database_Libs1") (part "C"))
    )
    (comp (ref "C291")
      (value "100nF")
      (footprint "SMD_0603_CAPC1608X95N")
      (fields
        (field (name "DB_PART_NUMBER") "CAP000027236")
        (field (name "DB_VALUE") "100nF")
        (field (name "DB_TOLERANCE") "20%")
        (field (name "DB_VOLTAGE") "16V")
        (field (name "DB_MANUFACTURER_PART") "KEMET    C0603C104M4RAC")
        (field (name "DB_APPROVED_BY") "ISHIDDEN=T")
      )
      (libsource (lib "Database_Libs1") (part "C"))
    )
    (comp (ref "C293")
      (value "100nF")
      (footprint "SMD_0603_CAPC1608X95N")
      (fields
        (field (name "DB_PART_NUMBER") "CAP000027236")
        (field (name "DB_VALUE") "100nF")
        (field (name "DB_TOLERANCE") "20%")
        (field (name "DB_VOLTAGE") "16V")
        (field (name "DB_MANUFACTURER_PART") "KEMET    C0603C104M4RAC")
        (field (name "DB_APPROVED_BY") "ISHIDDEN=T")
      )
      (libsource (lib "Database_Libs1") (part "C"))
    )
    (comp (ref "C294")
      (value "100nF")
      (footprint "SMD_0603_CAPC1608X95N")
      (fields
        (field (name "DB_PART_NUMBER") "CAP000027236")
        (field (name "DB_VALUE") "100nF")
        (field (name "DB_TOLERANCE") "20%")
        (field (name "DB_VOLTAGE") "16V")
        (field (name "DB_MANUFACTURER_PART") "KEMET    C0603C104M4RAC")
        (field (name "DB_APPROVED_BY") "ISHIDDEN=T")
      )
      (libsource (lib "Database_Libs1") (part "C"))
    )
    (comp (ref "C303")
      (value "100nF")
      (footprint "SMD_0603_CAPC1608X95N")
      (fields
        (field (name "DB_PART_NUMBER") "CAP000027236")
        (field (name "DB_VALUE") "100nF")
        (field (name "DB_TOLERANCE") "20%")
        (field (name "DB_VOLTAGE") "16V")
        (field (name "DB_MANUFACTURER_PART") "KEMET    C0603C104M4RAC")
        (field (name "DB_APPROVED_BY") "ISHIDDEN=T")
      )
      (libsource (lib "Database_Libs1") (part "C"))
    )
    (comp (ref "C304")
      (value "100nF")
      (footprint "SMD_0603_CAPC1608X95N")
      (fields
        (field (name "DB_PART_NUMBER") "CAP000027236")
        (field (name "DB_VALUE") "100nF")
        (field (name "DB_TOLERANCE") "20%")
        (field (name "DB_VOLTAGE") "16V")
        (field (name "DB_MANUFACTURER_PART") "KEMET    C0603C104M4RAC")
        (field (name "DB_APPROVED_BY") "ISHIDDEN=T")
      )
      (libsource (lib "Database_Libs1") (part "C"))
    )
    (comp (ref "C305")
      (value "100nF")
      (footprint "SMD_0603_CAPC1608X95N")
      (fields
        (field (name "DB_PART_NUMBER") "CAP000027236")
        (field (name "DB_VALUE") "100nF")
        (field (name "DB_TOLERANCE") "20%")
        (field (name "DB_VOLTAGE") "16V")
        (field (name "DB_MANUFACTURER_PART") "KEMET    C0603C104M4RAC")
        (field (name "DB_APPROVED_BY") "ISHIDDEN=T")
      )
      (libsource (lib "Database_Libs1") (part "C"))
    )
    (comp (ref "C306")
      (value "100nF")
      (footprint "SMD_0603_CAPC1608X95N")
      (fields
        (field (name "DB_PART_NUMBER") "CAP000027236")
        (field (name "DB_VALUE") "100nF")
        (field (name "DB_TOLERANCE") "20%")
        (field (name "DB_VOLTAGE") "16V")
        (field (name "DB_MANUFACTURER_PART") "KEMET    C0603C104M4RAC")
        (field (name "DB_APPROVED_BY") "ISHIDDEN=T")
      )
      (libsource (lib "Database_Libs1") (part "C"))
    )
    (comp (ref "C307")
      (value "100nF")
      (footprint "SMD_0603_CAPC1608X95N")
      (fields
        (field (name "DB_PART_NUMBER") "CAP000027236")
        (field (name "DB_VALUE") "100nF")
        (field (name "DB_TOLERANCE") "20%")
        (field (name "DB_VOLTAGE") "16V")
        (field (name "DB_MANUFACTURER_PART") "KEMET    C0603C104M4RAC")
        (field (name "DB_APPROVED_BY") "ISHIDDEN=T")
      )
      (libsource (lib "Database_Libs1") (part "C"))
    )
    (comp (ref "C309")
      (value "100nF")
      (footprint "SMD_0603_CAPC1608X95N")
      (fields
        (field (name "DB_PART_NUMBER") "CAP000027236")
        (field (name "DB_VALUE") "100nF")
        (field (name "DB_TOLERANCE") "20%")
        (field (name "DB_VOLTAGE") "16V")
        (field (name "DB_MANUFACTURER_PART") "KEMET    C0603C104M4RAC")
        (field (name "DB_APPROVED_BY") "ISHIDDEN=T")
      )
      (libsource (lib "Database_Libs1") (part "C"))
    )
    (comp (ref "C315")
      (value "100nF")
      (footprint "SMD_0603_CAPC1608X95N")
      (fields
        (field (name "DB_PART_NUMBER") "CAP000027236")
        (field (name "DB_VALUE") "100nF")
        (field (name "DB_TOLERANCE") "20%")
        (field (name "DB_VOLTAGE") "16V")
        (field (name "DB_MANUFACTURER_PART") "KEMET    C0603C104M4RAC")
        (field (name "DB_APPROVED_BY") "ISHIDDEN=T")
      )
      (libsource (lib "Database_Libs1") (part "C"))
    )
    (comp (ref "C322")
      (value "100nF")
      (footprint "SMD_0603_CAPC1608X95N")
      (fields
        (field (name "DB_PART_NUMBER") "CAP000027236")
        (field (name "DB_VALUE") "100nF")
        (field (name "DB_TOLERANCE") "20%")
        (field (name "DB_VOLTAGE") "16V")
        (field (name "DB_MANUFACTURER_PART") "KEMET    C0603C104M4RAC")
        (field (name "DB_APPROVED_BY") "ISHIDDEN=T")
      )
      (libsource (lib "Database_Libs1") (part "C"))
    )
    (comp (ref "C594")
      (value "100nF")
      (footprint "SMD_0603_CAPC1608X95N")
      (fields
        (field (name "DB_PART_NUMBER") "CAP000027236")
        (field (name "DB_VALUE") "100nF")
        (field (name "DB_TOLERANCE") "20%")
        (field (name "DB_VOLTAGE") "16V")
        (field (name "DB_MANUFACTURER_PART") "KEMET    C0603C104M4RAC")
        (field (name "DB_APPROVED_BY") "ISHIDDEN=T")
      )
      (libsource (lib "Database_Libs1") (part "C"))
    )
    (comp (ref "C595")
      (value "100nF")
      (footprint "SMD_0603_CAPC1608X95N")
      (fields
        (field (name "DB_PART_NUMBER") "CAP000027236")
        (field (name "DB_VALUE") "100nF")
        (field (name "DB_TOLERANCE") "20%")
        (field (name "DB_VOLTAGE") "16V")
        (field (name "DB_MANUFACTURER_PART") "KEMET    C0603C104M4RAC")
        (field (name "DB_APPROVED_BY") "ISHIDDEN=T")
      )
      (libsource (lib "Database_Libs1") (part "C"))
    )
    (comp (ref "C597")
      (value "100nF")
      (footprint "SMD_0603_CAPC1608X95N")
      (fields
        (field (name "DB_PART_NUMBER") "CAP000027236")
        (field (name "DB_VALUE") "100nF")
        (field (name "DB_TOLERANCE") "20%")
        (field (name "DB_VOLTAGE") "16V")
        (field (name "DB_MANUFACTURER_PART") "KEMET    C0603C104M4RAC")
        (field (name "DB_APPROVED_BY") "ISHIDDEN=T")
      )
      (libsource (lib "Database_Libs1") (part "C"))
    )
    (comp (ref "C601")
      (value "100nF")
      (footprint "SMD_0603_CAPC1608X95N")
      (fields
        (field (name "DB_PART_NUMBER") "CAP000027236")
        (field (name "DB_VALUE") "100nF")
        (field (name "DB_TOLERANCE") "20%")
        (field (name "DB_VOLTAGE") "16V")
        (field (name "DB_MANUFACTURER_PART") "KEMET    C0603C104M4RAC")
        (field (name "DB_APPROVED_BY") "ISHIDDEN=T")
      )
      (libsource (lib "Database_Libs1") (part "C"))
    )
    (comp (ref "C604")
      (value "100nF")
      (footprint "SMD_0603_CAPC1608X95N")
      (fields
        (field (name "DB_PART_NUMBER") "CAP000027236")
        (field (name "DB_VALUE") "100nF")
        (field (name "DB_TOLERANCE") "20%")
        (field (name "DB_VOLTAGE") "16V")
        (field (name "DB_MANUFACTURER_PART") "KEMET    C0603C104M4RAC")
        (field (name "DB_APPROVED_BY") "ISHIDDEN=T")
      )
      (libsource (lib "Database_Libs1") (part "C"))
    )
    (comp (ref "C609")
      (value "100nF")
      (footprint "SMD_0603_CAPC1608X95N")
      (fields
        (field (name "DB_PART_NUMBER") "CAP000027236")
        (field (name "DB_VALUE") "100nF")
        (field (name "DB_TOLERANCE") "20%")
        (field (name "DB_VOLTAGE") "16V")
        (field (name "DB_MANUFACTURER_PART") "KEMET    C0603C104M4RAC")
        (field (name "DB_APPROVED_BY") "ISHIDDEN=T")
      )
      (libsource (lib "Database_Libs1") (part "C"))
    )
    (comp (ref "C610")
      (value "100nF")
      (footprint "SMD_0603_CAPC1608X95N")
      (fields
        (field (name "DB_PART_NUMBER") "CAP000027236")
        (field (name "DB_VALUE") "100nF")
        (field (name "DB_TOLERANCE") "20%")
        (field (name "DB_VOLTAGE") "16V")
        (field (name "DB_MANUFACTURER_PART") "KEMET    C0603C104M4RAC")
        (field (name "DB_APPROVED_BY") "ISHIDDEN=T")
      )
      (libsource (lib "Database_Libs1") (part "C"))
    )
    (comp (ref "C616")
      (value "100nF")
      (footprint "SMD_0603_CAPC1608X95N")
      (fields
        (field (name "DB_PART_NUMBER") "CAP000027236")
        (field (name "DB_VALUE") "100nF")
        (field (name "DB_TOLERANCE") "20%")
        (field (name "DB_VOLTAGE") "16V")
        (field (name "DB_MANUFACTURER_PART") "KEMET    C0603C104M4RAC")
        (field (name "DB_APPROVED_BY") "ISHIDDEN=T")
      )
      (libsource (lib "Database_Libs1") (part "C"))
    )
    (comp (ref "D5")
      (value "KP-2012EC")
      (footprint "SMD_0805_LED2012X100N")
      (fields
        (field (name "DB_PART_NUMBER") "OPT000000095")
        (field (name "DB_MANUFACTURER_PART") "KINGBRIGHT       KP-2012EC")
        (field (name "DB_VALUE") "KP-2012EC")
        (field (name "DB_APPROVED_BY") "VSN")
      )
      (libsource (lib "Database_Libs1") (part "LED"))
    )
    (comp (ref "D7")
      (value "KP-2012CGCK")
      (footprint "SMD_0805_LED2012X100N")
      (fields
        (field (name "DB_PART_NUMBER") "OPT000000096")
        (field (name "DB_MANUFACTURER_PART") "KINGBRIGHT       KP-2012CGCK")
        (field (name "DB_VALUE") "KP-2012CGCK")
        (field (name "DB_APPROVED_BY") "VSN")
      )
      (libsource (lib "Database_Libs1") (part "LED"))
    )
    (comp (ref "D9")
      (value "17-21-Y2C-A0L1M2V0B-3T-AM")
      (footprint "SMD_0805_LED2012X100N")
      (fields
        (field (name "DB_PART_NUMBER") "OPT000000092")
        (field (name "DB_MANUFACTURER_PART") "EVERLIGHT       17-21-Y2C-A0L1M2V0B-3T-AM")
        (field (name "DB_VALUE") "17-21-Y2C-A0L1M2V0B-3T-AM")
        (field (name "DB_APPROVED_BY") "VSN")
      )
      (libsource (lib "Database_Libs1") (part "LED"))
    )
    (comp (ref "D12")
      (value "KP-2012EC")
      (footprint "SMD_0805_LED2012X100N")
      (fields
        (field (name "DB_PART_NUMBER") "OPT000000095")
        (field (name "DB_MANUFACTURER_PART") "KINGBRIGHT       KP-2012EC")
        (field (name "DB_VALUE") "KP-2012EC")
        (field (name "DB_APPROVED_BY") "VSN")
      )
      (libsource (lib "Database_Libs1") (part "LED"))
    )
    (comp (ref "D13")
      (value "KP-2012CGCK")
      (footprint "SMD_0805_LED2012X100N")
      (fields
        (field (name "DB_PART_NUMBER") "OPT000000096")
        (field (name "DB_MANUFACTURER_PART") "KINGBRIGHT       KP-2012CGCK")
        (field (name "DB_VALUE") "KP-2012CGCK")
        (field (name "DB_APPROVED_BY") "VSN")
      )
      (libsource (lib "Database_Libs1") (part "LED"))
    )
    (comp (ref "D16")
      (value "17-21-Y2C-A0L1M2V0B-3T-AM")
      (footprint "SMD_0805_LED2012X100N")
      (fields
        (field (name "DB_PART_NUMBER") "OPT000000092")
        (field (name "DB_MANUFACTURER_PART") "EVERLIGHT       17-21-Y2C-A0L1M2V0B-3T-AM")
        (field (name "DB_VALUE") "17-21-Y2C-A0L1M2V0B-3T-AM")
        (field (name "DB_APPROVED_BY") "VSN")
      )
      (libsource (lib "Database_Libs1") (part "LED"))
    )
    (comp (ref "D17")
      (value "KP-2012CGCK")
      (footprint "SMD_0805_LED2012X100N")
      (fields
        (field (name "DB_PART_NUMBER") "OPT000000096")
        (field (name "DB_MANUFACTURER_PART") "KINGBRIGHT       KP-2012CGCK")
        (field (name "DB_APPROVED_BY") "VSN")
      )
      (libsource (lib "altium-import") (part "root_0_LED_Orange_"))
    )
    (comp (ref "D20")
      (value "KP-2012EC")
      (footprint "SMD_0805_LED2012X100N")
      (fields
        (field (name "DB_PART_NUMBER") "OPT000000095")
        (field (name "DB_MANUFACTURER_PART") "KINGBRIGHT       KP-2012EC")
        (field (name "DB_VALUE") "KP-2012EC")
        (field (name "DB_APPROVED_BY") "VSN")
      )
      (libsource (lib "Database_Libs1") (part "LED"))
    )
    (comp (ref "D21")
      (value "KP-2012EC")
      (footprint "SMD_0805_LED2012X100N")
      (fields
        (field (name "DB_PART_NUMBER") "OPT000000095")
        (field (name "DB_MANUFACTURER_PART") "KINGBRIGHT       KP-2012EC")
        (field (name "DB_VALUE") "KP-2012EC")
        (field (name "DB_APPROVED_BY") "VSN")
      )
      (libsource (lib "Database_Libs1") (part "LED"))
    )
    (comp (ref "D24")
      (value "KP-2012CGCK")
      (footprint "SMD_0805_LED2012X100N")
      (fields
        (field (name "DB_PART_NUMBER") "OPT000000096")
        (field (name "DB_MANUFACTURER_PART") "KINGBRIGHT       KP-2012CGCK")
        (field (name "DB_VALUE") "KP-2012CGCK")
        (field (name "DB_APPROVED_BY") "VSN")
      )
      (libsource (lib "Database_Libs1") (part "LED"))
    )
    (comp (ref "D25")
      (value "KP-2012CGCK")
      (footprint "SMD_0805_LED2012X100N")
      (fields
        (field (name "DB_PART_NUMBER") "OPT000000096")
        (field (name "DB_MANUFACTURER_PART") "KINGBRIGHT       KP-2012CGCK")
        (field (name "DB_VALUE") "KP-2012CGCK")
        (field (name "DB_APPROVED_BY") "VSN")
      )
      (libsource (lib "Database_Libs1") (part "LED"))
    )
    (comp (ref "D27")
      (value "17-21-Y2C-A0L1M2V0B-3T-AM")
      (footprint "SMD_0805_LED2012X100N")
      (fields
        (field (name "DB_PART_NUMBER") "OPT000000092")
        (field (name "DB_MANUFACTURER_PART") "EVERLIGHT       17-21-Y2C-A0L1M2V0B-3T-AM")
        (field (name "DB_VALUE") "17-21-Y2C-A0L1M2V0B-3T-AM")
        (field (name "DB_APPROVED_BY") "VSN")
      )
      (libsource (lib "Database_Libs1") (part "LED"))
    )
    (comp (ref "D29")
      (value "17-21-Y2C-A0L1M2V0B-3T-AM")
      (footprint "SMD_0805_LED2012X100N")
      (fields
        (field (name "DB_PART_NUMBER") "OPT000000092")
        (field (name "DB_MANUFACTURER_PART") "EVERLIGHT       17-21-Y2C-A0L1M2V0B-3T-AM")
        (field (name "DB_VALUE") "17-21-Y2C-A0L1M2V0B-3T-AM")
        (field (name "DB_APPROVED_BY") "VSN")
      )
      (libsource (lib "Database_Libs1") (part "LED"))
    )
    (comp (ref "D31")
      (value "KP-2012CGCK")
      (footprint "SMD_0805_LED2012X100N")
      (fields
        (field (name "DB_PART_NUMBER") "OPT000000096")
        (field (name "DB_MANUFACTURER_PART") "KINGBRIGHT       KP-2012CGCK")
        (field (name "DB_APPROVED_BY") "VSN")
      )
      (libsource (lib "altium-import") (part "root_0_LED_Orange_"))
    )
    (comp (ref "D33")
      (value "KP-2012EC")
      (footprint "SMD_0805_LED2012X100N")
      (fields
        (field (name "DB_PART_NUMBER") "OPT000000095")
        (field (name "DB_MANUFACTURER_PART") "KINGBRIGHT       KP-2012EC")
        (field (name "DB_VALUE") "KP-2012EC")
        (field (name "DB_APPROVED_BY") "VSN")
      )
      (libsource (lib "Database_Libs1") (part "LED"))
    )
    (comp (ref "D34")
      (value "KP-2012EC")
      (footprint "SMD_0805_LED2012X100N")
      (fields
        (field (name "DB_PART_NUMBER") "OPT000000095")
        (field (name "DB_MANUFACTURER_PART") "KINGBRIGHT       KP-2012EC")
        (field (name "DB_VALUE") "KP-2012EC")
        (field (name "DB_APPROVED_BY") "VSN")
      )
      (libsource (lib "Database_Libs1") (part "LED"))
    )
    (comp (ref "D35")
      (value "KP-2012CGCK")
      (footprint "SMD_0805_LED2012X100N")
      (fields
        (field (name "DB_PART_NUMBER") "OPT000000096")
        (field (name "DB_MANUFACTURER_PART") "KINGBRIGHT       KP-2012CGCK")
        (field (name "DB_VALUE") "KP-2012CGCK")
        (field (name "DB_APPROVED_BY") "VSN")
      )
      (libsource (lib "Database_Libs1") (part "LED"))
    )
    (comp (ref "D36")
      (value "KP-2012CGCK")
      (footprint "SMD_0805_LED2012X100N")
      (fields
        (field (name "DB_PART_NUMBER") "OPT000000096")
        (field (name "DB_MANUFACTURER_PART") "KINGBRIGHT       KP-2012CGCK")
        (field (name "DB_VALUE") "KP-2012CGCK")
        (field (name "DB_APPROVED_BY") "VSN")
      )
      (libsource (lib "Database_Libs1") (part "LED"))
    )
    (comp (ref "D37")
      (value "17-21-Y2C-A0L1M2V0B-3T-AM")
      (footprint "SMD_0805_LED2012X100N")
      (fields
        (field (name "DB_PART_NUMBER") "OPT000000092")
        (field (name "DB_MANUFACTURER_PART") "EVERLIGHT       17-21-Y2C-A0L1M2V0B-3T-AM")
        (field (name "DB_VALUE") "17-21-Y2C-A0L1M2V0B-3T-AM")
        (field (name "DB_APPROVED_BY") "VSN")
      )
      (libsource (lib "Database_Libs1") (part "LED"))
    )
    (comp (ref "D38")
      (value "17-21-Y2C-A0L1M2V0B-3T-AM")
      (footprint "SMD_0805_LED2012X100N")
      (fields
        (field (name "DB_PART_NUMBER") "OPT000000092")
        (field (name "DB_MANUFACTURER_PART") "EVERLIGHT       17-21-Y2C-A0L1M2V0B-3T-AM")
        (field (name "DB_VALUE") "17-21-Y2C-A0L1M2V0B-3T-AM")
        (field (name "DB_APPROVED_BY") "VSN")
      )
      (libsource (lib "Database_Libs1") (part "LED"))
    )
    (comp (ref "D39")
      (value "KP-2012CGCK")
      (footprint "SMD_0805_LED2012X100N")
      (fields
        (field (name "DB_PART_NUMBER") "OPT000000096")
        (field (name "DB_MANUFACTURER_PART") "KINGBRIGHT       KP-2012CGCK")
        (field (name "DB_APPROVED_BY") "VSN")
      )
      (libsource (lib "altium-import") (part "root_0_LED_Orange_"))
    )
    (comp (ref "D40")
      (value "KP-2012EC")
      (footprint "SMD_0805_LED2012X100N")
      (fields
        (field (name "DB_PART_NUMBER") "OPT000000095")
        (field (name "DB_MANUFACTURER_PART") "KINGBRIGHT       KP-2012EC")
        (field (name "DB_VALUE") "KP-2012EC")
        (field (name "DB_APPROVED_BY") "VSN")
      )
      (libsource (lib "Database_Libs1") (part "LED"))
    )
    (comp (ref "D41")
      (value "KP-2012EC")
      (footprint "SMD_0805_LED2012X100N")
      (fields
        (field (name "DB_PART_NUMBER") "OPT000000095")
        (field (name "DB_MANUFACTURER_PART") "KINGBRIGHT       KP-2012EC")
        (field (name "DB_VALUE") "KP-2012EC")
        (field (name "DB_APPROVED_BY") "VSN")
      )
      (libsource (lib "Database_Libs1") (part "LED"))
    )
    (comp (ref "D42")
      (value "KP-2012CGCK")
      (footprint "SMD_0805_LED2012X100N")
      (fields
        (field (name "DB_PART_NUMBER") "OPT000000096")
        (field (name "DB_MANUFACTURER_PART") "KINGBRIGHT       KP-2012CGCK")
        (field (name "DB_VALUE") "KP-2012CGCK")
        (field (name "DB_APPROVED_BY") "VSN")
      )
      (libsource (lib "Database_Libs1") (part "LED"))
    )
    (comp (ref "D43")
      (value "KP-2012CGCK")
      (footprint "SMD_0805_LED2012X100N")
      (fields
        (field (name "DB_PART_NUMBER") "OPT000000096")
        (field (name "DB_MANUFACTURER_PART") "KINGBRIGHT       KP-2012CGCK")
        (field (name "DB_VALUE") "KP-2012CGCK")
        (field (name "DB_APPROVED_BY") "VSN")
      )
      (libsource (lib "Database_Libs1") (part "LED"))
    )
    (comp (ref "D44")
      (value "17-21-Y2C-A0L1M2V0B-3T-AM")
      (footprint "SMD_0805_LED2012X100N")
      (fields
        (field (name "DB_PART_NUMBER") "OPT000000092")
        (field (name "DB_MANUFACTURER_PART") "EVERLIGHT       17-21-Y2C-A0L1M2V0B-3T-AM")
        (field (name "DB_VALUE") "17-21-Y2C-A0L1M2V0B-3T-AM")
        (field (name "DB_APPROVED_BY") "VSN")
      )
      (libsource (lib "Database_Libs1") (part "LED"))
    )
    (comp (ref "D45")
      (value "17-21-Y2C-A0L1M2V0B-3T-AM")
      (footprint "SMD_0805_LED2012X100N")
      (fields
        (field (name "DB_PART_NUMBER") "OPT000000092")
        (field (name "DB_MANUFACTURER_PART") "EVERLIGHT       17-21-Y2C-A0L1M2V0B-3T-AM")
        (field (name "DB_VALUE") "17-21-Y2C-A0L1M2V0B-3T-AM")
        (field (name "DB_APPROVED_BY") "VSN")
      )
      (libsource (lib "Database_Libs1") (part "LED"))
    )
    (comp (ref "D46")
      (value "KP-2012CGCK")
      (footprint "SMD_0805_LED2012X100N")
      (fields
        (field (name "DB_PART_NUMBER") "OPT000000096")
        (field (name "DB_MANUFACTURER_PART") "KINGBRIGHT       KP-2012CGCK")
        (field (name "DB_APPROVED_BY") "VSN")
      )
      (libsource (lib "altium-import") (part "root_0_LED_Orange_"))
    )
    (comp (ref "R1")
      (value "0R")
      (footprint "SMD_0603_RESC1608X55N")
      (fields
        (field (name "DB_PART_NUMBER") "RES000006349")
        (field (name "DB_VALUE") "0R")
        (field (name "DB_TOLERANCE") "5%")
        (field (name "DB_MANUFACTURER_PART") "YAGEO    RC0603JR-070R")
        (field (name "DB_APPROVED_BY") "ISHIDDEN=T")
      )
      (libsource (lib "Database_Libs1") (part "R"))
    )
    (comp (ref "R2")
      (value "0R")
      (footprint "SMD_0603_RESC1608X55N")
      (fields
        (field (name "DB_PART_NUMBER") "RES000006349")
        (field (name "DB_VALUE") "0R")
        (field (name "DB_TOLERANCE") "5%")
        (field (name "DB_MANUFACTURER_PART") "YAGEO    RC0603JR-070R")
        (field (name "DB_APPROVED_BY") "ISHIDDEN=T")
      )
      (libsource (lib "Database_Libs1") (part "R"))
    )
    (comp (ref "R3")
      (value "0R")
      (footprint "SMD_0603_RESC1608X55N")
      (fields
        (field (name "DB_PART_NUMBER") "RES000006349")
        (field (name "DB_VALUE") "0R")
        (field (name "DB_TOLERANCE") "5%")
        (field (name "DB_MANUFACTURER_PART") "YAGEO    RC0603JR-070R")
        (field (name "DB_APPROVED_BY") "ISHIDDEN=T")
      )
      (libsource (lib "Database_Libs1") (part "R"))
    )
    (comp (ref "R19")
      (value "0R")
      (footprint "SMD_0603_RESC1608X55N")
      (fields
        (field (name "DB_PART_NUMBER") "RES000006349")
        (field (name "DB_VALUE") "0R")
        (field (name "DB_TOLERANCE") "5%")
        (field (name "DB_MANUFACTURER_PART") "YAGEO    RC0603JR-070R")
        (field (name "DB_APPROVED_BY") "ISHIDDEN=T")
      )
      (libsource (lib "Database_Libs1") (part "R"))
    )
    (comp (ref "R25")
      (value "0R")
      (footprint "SMD_0603_RESC1608X55N")
      (fields
        (field (name "DB_PART_NUMBER") "RES000006349")
        (field (name "DB_VALUE") "0R")
        (field (name "DB_TOLERANCE") "5%")
        (field (name "DB_MANUFACTURER_PART") "YAGEO    RC0603JR-070R")
        (field (name "DB_APPROVED_BY") "ISHIDDEN=T")
      )
      (libsource (lib "Database_Libs1") (part "R"))
    )
    (comp (ref "R37")
      (value "0R")
      (footprint "SMD_0603_RESC1608X55N")
      (fields
        (field (name "DB_PART_NUMBER") "RES000006349")
        (field (name "DB_VALUE") "0R")
        (field (name "DB_TOLERANCE") "5%")
        (field (name "DB_MANUFACTURER_PART") "YAGEO    RC0603JR-070R")
        (field (name "DB_APPROVED_BY") "ISHIDDEN=T")
      )
      (libsource (lib "Database_Libs1") (part "R"))
    )
    (comp (ref "R38")
      (value "0R")
      (footprint "SMD_0603_RESC1608X55N")
      (fields
        (field (name "DB_PART_NUMBER") "RES000006349")
        (field (name "DB_VALUE") "0R")
        (field (name "DB_TOLERANCE") "5%")
        (field (name "DB_MANUFACTURER_PART") "YAGEO    RC0603JR-070R")
        (field (name "DB_APPROVED_BY") "ISHIDDEN=T")
      )
      (libsource (lib "Database_Libs1") (part "R"))
    )
    (comp (ref "R39")
      (value "0R")
      (footprint "SMD_0603_RESC1608X55N")
      (fields
        (field (name "DB_PART_NUMBER") "RES000006349")
        (field (name "DB_VALUE") "0R")
        (field (name "DB_TOLERANCE") "5%")
        (field (name "DB_MANUFACTURER_PART") "YAGEO    RC0603JR-070R")
        (field (name "DB_APPROVED_BY") "ISHIDDEN=T")
      )
      (libsource (lib "Database_Libs1") (part "R"))
    )
    (comp (ref "R40")
      (value "0R")
      (footprint "SMD_0603_RESC1608X55N")
      (fields
        (field (name "DB_PART_NUMBER") "RES000006349")
        (field (name "DB_VALUE") "0R")
        (field (name "DB_TOLERANCE") "5%")
        (field (name "DB_MANUFACTURER_PART") "YAGEO    RC0603JR-070R")
        (field (name "DB_APPROVED_BY") "ISHIDDEN=T")
      )
      (libsource (lib "Database_Libs1") (part "R"))
    )
    (comp (ref "R41")
      (value "0R")
      (footprint "SMD_0603_RESC1608X55N")
      (fields
        (field (name "DB_PART_NUMBER") "RES000006349")
        (field (name "DB_VALUE") "0R")
        (field (name "DB_TOLERANCE") "5%")
        (field (name "DB_MANUFACTURER_PART") "YAGEO    RC0603JR-070R")
        (field (name "DB_APPROVED_BY") "ISHIDDEN=T")
      )
      (libsource (lib "Database_Libs1") (part "R"))
    )
    (comp (ref "R42")
      (value "0R")
      (footprint "SMD_0603_RESC1608X55N")
      (fields
        (field (name "DB_PART_NUMBER") "RES000006349")
        (field (name "DB_VALUE") "0R")
        (field (name "DB_TOLERANCE") "5%")
        (field (name "DB_MANUFACTURER_PART") "YAGEO    RC0603JR-070R")
        (field (name "DB_APPROVED_BY") "ISHIDDEN=T")
      )
      (libsource (lib "Database_Libs1") (part "R"))
    )
    (comp (ref "TP1")
      (value "100_254")
      (footprint "SMD_TP_100-254")
      (fields
        (field (name "DB_PART_NUMBER") "TPO000000001")
        (field (name "DB_MANUFACTURER_PART") "ISHIDDEN=T")
        (field (name "DB_APPROVED_BY") "ISHIDDEN=T")
      )
      (libsource (lib "Database_Libs1") (part "TEST_POINT_1"))
    )
    (comp (ref "TP3")
      (value "100_254")
      (footprint "SMD_TP_100-254")
      (fields
        (field (name "DB_PART_NUMBER") "TPO000000001")
        (field (name "DB_MANUFACTURER_PART") "ISHIDDEN=T")
        (field (name "DB_APPROVED_BY") "ISHIDDEN=T")
      )
      (libsource (lib "Database_Libs1") (part "TEST_POINT_1"))
    )
    (comp (ref "TP4")
      (value "100_254")
      (footprint "SMD_TP_100-254")
      (fields
        (field (name "DB_PART_NUMBER") "TPO000000001")
        (field (name "DB_MANUFACTURER_PART") "ISHIDDEN=T")
        (field (name "DB_APPROVED_BY") "ISHIDDEN=T")
      )
      (libsource (lib "Database_Libs1") (part "TEST_POINT_1"))
    )
    (comp (ref "TP8")
      (value "100_254")
      (footprint "SMD_TP_100-254")
      (fields
        (field (name "DB_PART_NUMBER") "TPO000000001")
        (field (name "DB_MANUFACTURER_PART") "ISHIDDEN=T")
        (field (name "DB_APPROVED_BY") "ISHIDDEN=T")
      )
      (libsource (lib "Database_Libs1") (part "TEST_POINT_1"))
    )
    (comp (ref "TP9")
      (value "100_254")
      (footprint "SMD_TP_100-254")
      (fields
        (field (name "DB_PART_NUMBER") "TPO000000001")
        (field (name "DB_MANUFACTURER_PART") "ISHIDDEN=T")
        (field (name "DB_APPROVED_BY") "ISHIDDEN=T")
      )
      (libsource (lib "Database_Libs1") (part "TEST_POINT_1"))
    )
    (comp (ref "TP14")
      (value "100_254")
      (footprint "SMD_TP_100-254")
      (fields
        (field (name "DB_PART_NUMBER") "TPO000000001")
        (field (name "DB_MANUFACTURER_PART") "ISHIDDEN=T")
        (field (name "DB_APPROVED_BY") "ISHIDDEN=T")
      )
      (libsource (lib "Database_Libs1") (part "TEST_POINT_1"))
    )
    (comp (ref "TP15")
      (value "100_254")
      (footprint "SMD_TP_100-254")
      (fields
        (field (name "DB_PART_NUMBER") "TPO000000001")
        (field (name "DB_MANUFACTURER_PART") "ISHIDDEN=T")
        (field (name "DB_APPROVED_BY") "ISHIDDEN=T")
      )
      (libsource (lib "Database_Libs1") (part "TEST_POINT_1"))
    )
    (comp (ref "TP16")
      (value "100_254")
      (footprint "SMD_TP_100-254")
      (fields
        (field (name "DB_PART_NUMBER") "TPO000000001")
        (field (name "DB_MANUFACTURER_PART") "ISHIDDEN=T")
        (field (name "DB_APPROVED_BY") "ISHIDDEN=T")
      )
      (libsource (lib "Database_Libs1") (part "TEST_POINT_1"))
    )
    (comp (ref "U2")
      (value "~")
      (footprint "SMD_BGA900C80P30X30")
      (libsource (lib "Schlib1") (part "Minion 99s256"))
    )
    (comp (ref "U3")
      (value "~")
      (footprint "SMD_BGA900C80P30X30")
      (libsource (lib "Schlib1") (part "Minion 99s256"))
    )
    (comp (ref "U4")
      (value "~")
      (footprint "SMD_BGA900C80P30X30")
      (libsource (lib "Schlib1") (part "Minion 99s256"))
    )
    (comp (ref "U13")
      (value "~")
      (footprint "SMD_BGA900C80P30X30")
      (libsource (lib "Schlib1") (part "Minion 99s256"))
    )
    (comp (ref "YO1")
      (value "~")
      (footprint "SMD_OSCCF200X250X90-4N")
      (libsource (lib "Schlib1") (part "SMD_OSC_DFN_2X2.5MM"))
    )
    (comp (ref "YO2")
      (value "~")
      (footprint "SMD_OSCCF250X320X90-4N")
      (libsource (lib "Schlib1") (part "SMD_OSC_DFN_2.5X3.2MM"))
    )
    (comp (ref "YO3")
      (value "~")
      (footprint "SMD_OSCCF320X400X90-4N")
      (libsource (lib "Schlib1") (part "SMD_OSC_DFN_3.2x5mm"))
    )
    (comp (ref "YO4")
      (value "~")
      (footprint "SMD_OSCCF200X250X90-4N")
      (libsource (lib "Schlib1") (part "SMD_OSC_DFN_2X2.5MM"))
    )
    (comp (ref "YO5")
      (value "~")
      (footprint "SMD_OSCCF250X320X90-4N")
      (libsource (lib "Schlib1") (part "SMD_OSC_DFN_2.5X3.2MM"))
    )
    (comp (ref "YO6")
      (value "~")
      (footprint "SMD_OSCCF320X400X90-4N")
      (libsource (lib "Schlib1") (part "SMD_OSC_DFN_3.2x5mm"))
    )
    (comp (ref "YO7")
      (value "~")
      (footprint "SMD_OSCCC500X700X100-4N")
      (libsource (lib "Schlib1") (part "SMD_OSC_TA 7x5mm"))
    )
    (comp (ref "YO8")
      (value "~")
      (footprint "SMD_OSCCC500X700X100-4N")
      (libsource (lib "Schlib1") (part "SMD_OSC_TA 7x5mm"))
    )
    (comp (ref "YO9")
      (value "~")
      (footprint "SMD_OSCCF200X250X90-4N")
      (libsource (lib "Schlib1") (part "SMD_OSC_DFN_2X2.5MM"))
    )
    (comp (ref "YO10")
      (value "~")
      (footprint "SMD_OSCCF250X320X90-4N")
      (libsource (lib "Schlib1") (part "SMD_OSC_DFN_2.5X3.2MM"))
    )
    (comp (ref "YO11")
      (value "~")
      (footprint "SMD_OSCCF200X250X90-4N")
      (libsource (lib "Schlib1") (part "SMD_OSC_DFN_2X2.5MM"))
    )
    (comp (ref "YO12")
      (value "~")
      (footprint "SMD_OSCCF250X320X90-4N")
      (libsource (lib "Schlib1") (part "SMD_OSC_DFN_2.5X3.2MM"))
    )
    (comp (ref "YO13")
      (value "~")
      (footprint "SMD_OSCCF320X400X90-4N")
      (libsource (lib "Schlib1") (part "SMD_OSC_DFN_3.2x5mm"))
    )
    (comp (ref "YO14")
      (value "~")
      (footprint "SMD_OSCCC500X700X100-4N")
      (libsource (lib "Schlib1") (part "SMD_OSC_TA 7x5mm"))
    )
    (comp (ref "YO15")
      (value "~")
      (footprint "SMD_OSCCF320X400X90-4N")
      (libsource (lib "Schlib1") (part "SMD_OSC_DFN_3.2x5mm"))
    )
    (comp (ref "YO16")
      (value "~")
      (footprint "SMD_OSCCC500X700X100-4N")
      (libsource (lib "Schlib1") (part "SMD_OSC_TA 7x5mm"))
    )
  )
  (nets
    (net (code "1") (name "/0.9V") (class "Default")
      (node (ref "C304") (pin "2") (pinfunction "2_2") (pintype "passive"))
      (node (ref "C305") (pin "2") (pinfunction "2_2") (pintype "passive"))
      (node (ref "C306") (pin "2") (pinfunction "2_2") (pintype "passive"))
      (node (ref "C307") (pin "2") (pinfunction "2_2") (pintype "passive"))
      (node (ref "U13") (pin "AJ16") (pinfunction "PLL_AVDD2_AJ16") (pintype "passive"))
      (node (ref "U2") (pin "AJ16") (pinfunction "PLL_AVDD2_AJ16") (pintype "passive"))
      (node (ref "U3") (pin "AJ16") (pinfunction "PLL_AVDD2_AJ16") (pintype "passive"))
      (node (ref "U4") (pin "AJ16") (pinfunction "PLL_AVDD2_AJ16") (pintype "passive"))
    )
    (net (code "2") (name "/1.8V") (class "Default")
      (node (ref "C289") (pin "2") (pinfunction "2_2") (pintype "passive"))
      (node (ref "C291") (pin "2") (pinfunction "2_2") (pintype "passive"))
      (node (ref "C293") (pin "2") (pinfunction "2_2") (pintype "passive"))
      (node (ref "C294") (pin "2") (pinfunction "2_2") (pintype "passive"))
      (node (ref "U13") (pin "AJ12") (pinfunction "TSHUT_AVDD18_AJ12") (pintype "passive"))
      (node (ref "U13") (pin "AJ15") (pinfunction "PLL_AVDD_AJ15") (pintype "passive"))
      (node (ref "U13") (pin "AK13") (pinfunction "POR_AVDD18_AK13") (pintype "passive"))
      (node (ref "U2") (pin "AJ12") (pinfunction "TSHUT_AVDD18_AJ12") (pintype "passive"))
      (node (ref "U2") (pin "AJ15") (pinfunction "PLL_AVDD_AJ15") (pintype "passive"))
      (node (ref "U2") (pin "AK13") (pinfunction "POR_AVDD18_AK13") (pintype "passive"))
      (node (ref "U3") (pin "AJ12") (pinfunction "TSHUT_AVDD18_AJ12") (pintype "passive"))
      (node (ref "U3") (pin "AJ15") (pinfunction "PLL_AVDD_AJ15") (pintype "passive"))
      (node (ref "U3") (pin "AK13") (pinfunction "POR_AVDD18_AK13") (pintype "passive"))
      (node (ref "U4") (pin "AJ12") (pinfunction "TSHUT_AVDD18_AJ12") (pintype "passive"))
      (node (ref "U4") (pin "AJ15") (pinfunction "PLL_AVDD_AJ15") (pintype "passive"))
      (node (ref "U4") (pin "AK13") (pinfunction "POR_AVDD18_AK13") (pintype "passive"))
    )
    (net (code "3") (name "/1V") (class "Default")
      (node (ref "C106") (pin "2") (pinfunction "2_2") (pintype "passive"))
      (node (ref "C107") (pin "2") (pinfunction "2_2") (pintype "passive"))
      (node (ref "C108") (pin "2") (pinfunction "2_2") (pintype "passive"))
      (node (ref "C109") (pin "2") (pinfunction "2_2") (pintype "passive"))
      (node (ref "C110") (pin "2") (pinfunction "2_2") (pintype "passive"))
      (node (ref "C111") (pin "2") (pinfunction "2_2") (pintype "passive"))
      (node (ref "C112") (pin "2") (pinfunction "2_2") (pintype "passive"))
      (node (ref "C113") (pin "2") (pinfunction "2_2") (pintype "passive"))
      (node (ref "C114") (pin "2") (pinfunction "2_2") (pintype "passive"))
      (node (ref "C115") (pin "2") (pinfunction "2_2") (pintype "passive"))
      (node (ref "C118") (pin "2") (pinfunction "2_2") (pintype "passive"))
      (node (ref "C119") (pin "2") (pinfunction "2_2") (pintype "passive"))
      (node (ref "C122") (pin "2") (pinfunction "2_2") (pintype "passive"))
      (node (ref "C123") (pin "2") (pinfunction "2_2") (pintype "passive"))
      (node (ref "C126") (pin "2") (pinfunction "2_2") (pintype "passive"))
      (node (ref "C127") (pin "2") (pinfunction "2_2") (pintype "passive"))
      (node (ref "C138") (pin "2") (pinfunction "2_2") (pintype "passive"))
      (node (ref "C139") (pin "2") (pinfunction "2_2") (pintype "passive"))
      (node (ref "C140") (pin "2") (pinfunction "2_2") (pintype "passive"))
      (node (ref "C141") (pin "2") (pinfunction "2_2") (pintype "passive"))
      (node (ref "C142") (pin "2") (pinfunction "2_2") (pintype "passive"))
      (node (ref "C143") (pin "2") (pinfunction "2_2") (pintype "passive"))
      (node (ref "C144") (pin "2") (pinfunction "2_2") (pintype "passive"))
      (node (ref "C145") (pin "2") (pinfunction "2_2") (pintype "passive"))
      (node (ref "C146") (pin "2") (pinfunction "2_2") (pintype "passive"))
      (node (ref "C147") (pin "2") (pinfunction "2_2") (pintype "passive"))
      (node (ref "C148") (pin "2") (pinfunction "2_2") (pintype "passive"))
      (node (ref "C149") (pin "2") (pinfunction "2_2") (pintype "passive"))
      (node (ref "C150") (pin "2") (pinfunction "2_2") (pintype "passive"))
      (node (ref "C151") (pin "2") (pinfunction "2_2") (pintype "passive"))
      (node (ref "C152") (pin "2") (pinfunction "2_2") (pintype "passive"))
      (node (ref "C153") (pin "2") (pinfunction "2_2") (pintype "passive"))
      (node (ref "C154") (pin "2") (pinfunction "2_2") (pintype "passive"))
      (node (ref "C155") (pin "2") (pinfunction "2_2") (pintype "passive"))
      (node (ref "C156") (pin "2") (pinfunction "2_2") (pintype "passive"))
      (node (ref "C157") (pin "2") (pinfunction "2_2") (pintype "passive"))
      (node (ref "C158") (pin "2") (pinfunction "2_2") (pintype "passive"))
      (node (ref "C159") (pin "2") (pinfunction "2_2") (pintype "passive"))
      (node (ref "C160") (pin "2") (pinfunction "2_2") (pintype "passive"))
      (node (ref "C161") (pin "2") (pinfunction "2_2") (pintype "passive"))
      (node (ref "C162") (pin "2") (pinfunction "2_2") (pintype "passive"))
      (node (ref "C163") (pin "2") (pinfunction "2_2") (pintype "passive"))
      (node (ref "C164") (pin "2") (pinfunction "2_2") (pintype "passive"))
      (node (ref "C165") (pin "2") (pinfunction "2_2") (pintype "passive"))
      (node (ref "C166") (pin "2") (pinfunction "2_2") (pintype "passive"))
      (node (ref "C167") (pin "2") (pinfunction "2_2") (pintype "passive"))
      (node (ref "C169") (pin "2") (pinfunction "2_2") (pintype "passive"))
      (node (ref "C170") (pin "2") (pinfunction "2_2") (pintype "passive"))
      (node (ref "C171") (pin "2") (pinfunction "2_2") (pintype "passive"))
      (node (ref "C172") (pin "2") (pinfunction "2_2") (pintype "passive"))
      (node (ref "C173") (pin "2") (pinfunction "2_2") (pintype "passive"))
      (node (ref "C174") (pin "2") (pinfunction "2_2") (pintype "passive"))
      (node (ref "C175") (pin "2") (pinfunction "2_2") (pintype "passive"))
      (node (ref "C176") (pin "2") (pinfunction "2_2") (pintype "passive"))
      (node (ref "C177") (pin "2") (pinfunction "2_2") (pintype "passive"))
      (node (ref "C178") (pin "2") (pinfunction "2_2") (pintype "passive"))
      (node (ref "C179") (pin "2") (pinfunction "2_2") (pintype "passive"))
      (node (ref "C180") (pin "2") (pinfunction "2_2") (pintype "passive"))
      (node (ref "C19") (pin "2") (pinfunction "2_2") (pintype "passive"))
      (node (ref "C197") (pin "2") (pinfunction "2_2") (pintype "passive"))
      (node (ref "C198") (pin "2") (pinfunction "2_2") (pintype "passive"))
      (node (ref "C199") (pin "2") (pinfunction "2_2") (pintype "passive"))
      (node (ref "C200") (pin "2") (pinfunction "2_2") (pintype "passive"))
      (node (ref "C201") (pin "2") (pinfunction "2_2") (pintype "passive"))
      (node (ref "C202") (pin "2") (pinfunction "2_2") (pintype "passive"))
      (node (ref "C203") (pin "2") (pinfunction "2_2") (pintype "passive"))
      (node (ref "C204") (pin "2") (pinfunction "2_2") (pintype "passive"))
      (node (ref "C205") (pin "2") (pinfunction "2_2") (pintype "passive"))
      (node (ref "C206") (pin "2") (pinfunction "2_2") (pintype "passive"))
      (node (ref "C207") (pin "2") (pinfunction "2_2") (pintype "passive"))
      (node (ref "C208") (pin "2") (pinfunction "2_2") (pintype "passive"))
      (node (ref "C209") (pin "2") (pinfunction "2_2") (pintype "passive"))
      (node (ref "C210") (pin "2") (pinfunction "2_2") (pintype "passive"))
      (node (ref "C211") (pin "2") (pinfunction "2_2") (pintype "passive"))
      (node (ref "C212") (pin "2") (pinfunction "2_2") (pintype "passive"))
      (node (ref "C213") (pin "2") (pinfunction "2_2") (pintype "passive"))
      (node (ref "C214") (pin "2") (pinfunction "2_2") (pintype "passive"))
      (node (ref "C22") (pin "2") (pinfunction "2_2") (pintype "passive"))
      (node (ref "C23") (pin "2") (pinfunction "2_2") (pintype "passive"))
      (node (ref "C239") (pin "2") (pinfunction "2_2") (pintype "passive"))
      (node (ref "C26") (pin "2") (pinfunction "2_2") (pintype "passive"))
      (node (ref "C27") (pin "2") (pinfunction "2_2") (pintype "passive"))
      (node (ref "C30") (pin "2") (pinfunction "2_2") (pintype "passive"))
      (node (ref "C31") (pin "2") (pinfunction "2_2") (pintype "passive"))
      (node (ref "C36") (pin "2") (pinfunction "2_2") (pintype "passive"))
      (node (ref "C42") (pin "2") (pinfunction "2_2") (pintype "passive"))
      (node (ref "C43") (pin "2") (pinfunction "2_2") (pintype "passive"))
      (node (ref "C44") (pin "2") (pinfunction "2_2") (pintype "passive"))
      (node (ref "C45") (pin "2") (pinfunction "2_2") (pintype "passive"))
      (node (ref "C46") (pin "2") (pinfunction "2_2") (pintype "passive"))
      (node (ref "C47") (pin "2") (pinfunction "2_2") (pintype "passive"))
      (node (ref "C48") (pin "2") (pinfunction "2_2") (pintype "passive"))
      (node (ref "C49") (pin "2") (pinfunction "2_2") (pintype "passive"))
      (node (ref "C50") (pin "2") (pinfunction "2_2") (pintype "passive"))
      (node (ref "C51") (pin "2") (pinfunction "2_2") (pintype "passive"))
      (node (ref "C54") (pin "2") (pinfunction "2_2") (pintype "passive"))
      (node (ref "C55") (pin "2") (pinfunction "2_2") (pintype "passive"))
      (node (ref "C58") (pin "2") (pinfunction "2_2") (pintype "passive"))
      (node (ref "C59") (pin "2") (pinfunction "2_2") (pintype "passive"))
      (node (ref "C62") (pin "2") (pinfunction "2_2") (pintype "passive"))
      (node (ref "C63") (pin "2") (pinfunction "2_2") (pintype "passive"))
      (node (ref "C74") (pin "2") (pinfunction "2_2") (pintype "passive"))
      (node (ref "C75") (pin "2") (pinfunction "2_2") (pintype "passive"))
      (node (ref "C76") (pin "2") (pinfunction "2_2") (pintype "passive"))
      (node (ref "C77") (pin "2") (pinfunction "2_2") (pintype "passive"))
      (node (ref "C78") (pin "2") (pinfunction "2_2") (pintype "passive"))
      (node (ref "C79") (pin "2") (pinfunction "2_2") (pintype "passive"))
      (node (ref "C80") (pin "2") (pinfunction "2_2") (pintype "passive"))
      (node (ref "C81") (pin "2") (pinfunction "2_2") (pintype "passive"))
      (node (ref "C82") (pin "2") (pinfunction "2_2") (pintype "passive"))
      (node (ref "C83") (pin "2") (pinfunction "2_2") (pintype "passive"))
      (node (ref "C86") (pin "2") (pinfunction "2_2") (pintype "passive"))
      (node (ref "C87") (pin "2") (pinfunction "2_2") (pintype "passive"))
      (node (ref "C90") (pin "2") (pinfunction "2_2") (pintype "passive"))
      (node (ref "C91") (pin "2") (pinfunction "2_2") (pintype "passive"))
      (node (ref "C94") (pin "2") (pinfunction "2_2") (pintype "passive"))
      (node (ref "C95") (pin "2") (pinfunction "2_2") (pintype "passive"))
    )
    (net (code "4") (name "/3.3V") (class "Default")
      (node (ref "C303") (pin "2") (pinfunction "2_2") (pintype "passive"))
      (node (ref "C309") (pin "2") (pinfunction "2_2") (pintype "passive"))
      (node (ref "C315") (pin "2") (pinfunction "2_2") (pintype "passive"))
      (node (ref "C322") (pin "1") (pinfunction "1_1") (pintype "passive"))
      (node (ref "C604") (pin "1") (pinfunction "1_1") (pintype "passive"))
      (node (ref "C609") (pin "1") (pinfunction "1_1") (pintype "passive"))
      (node (ref "C610") (pin "1") (pinfunction "1_1") (pintype "passive"))
      (node (ref "C616") (pin "2") (pinfunction "2_2") (pintype "passive"))
      (node (ref "U13") (pin "AJ19") (pinfunction "IO_VDD_AJ19") (pintype "passive"))
      (node (ref "U13") (pin "AJ23") (pinfunction "IO_VDD_AJ23") (pintype "passive"))
      (node (ref "U13") (pin "AK10") (pinfunction "IO_VDD_AK10") (pintype "passive"))
      (node (ref "U13") (pin "AK4") (pinfunction "IO_VDD_AK4") (pintype "passive"))
      (node (ref "U13") (pin "AK6") (pinfunction "IO_VDD_AK6") (pintype "passive"))
      (node (ref "U2") (pin "AJ19") (pinfunction "IO_VDD_AJ19") (pintype "passive"))
      (node (ref "U2") (pin "AJ20") (pinfunction "CHIP_ADDR0_AJ20") (pintype "passive"))
      (node (ref "U2") (pin "AJ23") (pinfunction "IO_VDD_AJ23") (pintype "passive"))
      (node (ref "U2") (pin "AK10") (pinfunction "IO_VDD_AK10") (pintype "passive"))
      (node (ref "U2") (pin "AK4") (pinfunction "IO_VDD_AK4") (pintype "passive"))
      (node (ref "U2") (pin "AK6") (pinfunction "IO_VDD_AK6") (pintype "passive"))
      (node (ref "U3") (pin "AJ19") (pinfunction "IO_VDD_AJ19") (pintype "passive"))
      (node (ref "U3") (pin "AJ23") (pinfunction "IO_VDD_AJ23") (pintype "passive"))
      (node (ref "U3") (pin "AK10") (pinfunction "IO_VDD_AK10") (pintype "passive"))
      (node (ref "U3") (pin "AK21") (pinfunction "CHIP_ADDR1_AK21") (pintype "passive"))
      (node (ref "U3") (pin "AK4") (pinfunction "IO_VDD_AK4") (pintype "passive"))
      (node (ref "U3") (pin "AK6") (pinfunction "IO_VDD_AK6") (pintype "passive"))
      (node (ref "U4") (pin "AJ19") (pinfunction "IO_VDD_AJ19") (pintype "passive"))
      (node (ref "U4") (pin "AJ20") (pinfunction "CHIP_ADDR0_AJ20") (pintype "passive"))
      (node (ref "U4") (pin "AJ23") (pinfunction "IO_VDD_AJ23") (pintype "passive"))
      (node (ref "U4") (pin "AK10") (pinfunction "IO_VDD_AK10") (pintype "passive"))
      (node (ref "U4") (pin "AK21") (pinfunction "CHIP_ADDR1_AK21") (pintype "passive"))
      (node (ref "U4") (pin "AK4") (pinfunction "IO_VDD_AK4") (pintype "passive"))
      (node (ref "U4") (pin "AK6") (pinfunction "IO_VDD_AK6") (pintype "passive"))
      (node (ref "YO1") (pin "1") (pinfunction "OE_1") (pintype "passive"))
      (node (ref "YO1") (pin "4") (pinfunction "VDD_4") (pintype "passive"))
      (node (ref "YO10") (pin "1") (pinfunction "OE_1") (pintype "passive"))
      (node (ref "YO10") (pin "4") (pinfunction "VDD_4") (pintype "passive"))
      (node (ref "YO11") (pin "1") (pinfunction "OE_1") (pintype "passive"))
      (node (ref "YO11") (pin "4") (pinfunction "VDD_4") (pintype "passive"))
      (node (ref "YO12") (pin "1") (pinfunction "OE_1") (pintype "passive"))
      (node (ref "YO12") (pin "4") (pinfunction "VDD_4") (pintype "passive"))
      (node (ref "YO13") (pin "1") (pinfunction "OE_1") (pintype "passive"))
      (node (ref "YO13") (pin "4") (pinfunction "VDD_4") (pintype "passive"))
      (node (ref "YO14") (pin "1") (pinfunction "OE_1") (pintype "passive"))
      (node (ref "YO14") (pin "4") (pinfunction "VDD_4") (pintype "passive"))
      (node (ref "YO15") (pin "1") (pinfunction "OE_1") (pintype "passive"))
      (node (ref "YO15") (pin "4") (pinfunction "VDD_4") (pintype "passive"))
      (node (ref "YO16") (pin "1") (pinfunction "OE_1") (pintype "passive"))
      (node (ref "YO16") (pin "4") (pinfunction "VDD_4") (pintype "passive"))
      (node (ref "YO2") (pin "1") (pinfunction "OE_1") (pintype "passive"))
      (node (ref "YO2") (pin "4") (pinfunction "VDD_4") (pintype "passive"))
      (node (ref "YO3") (pin "1") (pinfunction "OE_1") (pintype "passive"))
      (node (ref "YO3") (pin "4") (pinfunction "VDD_4") (pintype "passive"))
      (node (ref "YO4") (pin "1") (pinfunction "OE_1") (pintype "passive"))
      (node (ref "YO4") (pin "4") (pinfunction "VDD_4") (pintype "passive"))
      (node (ref "YO5") (pin "1") (pinfunction "OE_1") (pintype "passive"))
      (node (ref "YO5") (pin "4") (pinfunction "VDD_4") (pintype "passive"))
      (node (ref "YO6") (pin "1") (pinfunction "OE_1") (pintype "passive"))
      (node (ref "YO6") (pin "4") (pinfunction "VDD_4") (pintype "passive"))
      (node (ref "YO7") (pin "1") (pinfunction "OE_1") (pintype "passive"))
      (node (ref "YO7") (pin "4") (pinfunction "VDD_4") (pintype "passive"))
      (node (ref "YO8") (pin "1") (pinfunction "OE_1") (pintype "passive"))
      (node (ref "YO8") (pin "4") (pinfunction "VDD_4") (pintype "passive"))
      (node (ref "YO9") (pin "1") (pinfunction "OE_1") (pintype "passive"))
      (node (ref "YO9") (pin "4") (pinfunction "VDD_4") (pintype "passive"))
    )
    (net (code "5") (name "/INT_OUT1") (class "Default")
      (node (ref "TP1") (pin "1") (pinfunction "1_1") (pintype "passive"))
      (node (ref "U13") (pin "AK24") (pinfunction "INT_OUT_AK24") (pintype "passive"))
    )
    (net (code "6") (name "/INT_OUT2") (class "Default")
      (node (ref "TP3") (pin "1") (pinfunction "1_1") (pintype "passive"))
      (node (ref "U2") (pin "AK24") (pinfunction "INT_OUT_AK24") (pintype "passive"))
    )
    (net (code "7") (name "/INT_OUT3") (class "Default")
      (node (ref "TP4") (pin "1") (pinfunction "1_1") (pintype "passive"))
      (node (ref "U3") (pin "AK24") (pinfunction "INT_OUT_AK24") (pintype "passive"))
    )
    (net (code "8") (name "/INT_OUT4") (class "Default")
      (node (ref "TP8") (pin "1") (pinfunction "1_1") (pintype "passive"))
      (node (ref "U4") (pin "AK24") (pinfunction "INT_OUT_AK24") (pintype "passive"))
    )
    (net (code "9") (name "/LED_BUSY1") (class "Default")
      (node (ref "D12") (pin "2") (pinfunction "A_2") (pintype "passive"))
      (node (ref "U13") (pin "AK8") (pinfunction "LED_BUSY_AK8") (pintype "passive"))
    )
    (net (code "10") (name "/LED_BUSY2") (class "Default")
      (node (ref "D21") (pin "2") (pinfunction "A_2") (pintype "passive"))
      (node (ref "U2") (pin "AK8") (pinfunction "LED_BUSY_AK8") (pintype "passive"))
    )
    (net (code "11") (name "/LED_BUSY3") (class "Default")
      (node (ref "D34") (pin "2") (pinfunction "A_2") (pintype "passive"))
      (node (ref "U3") (pin "AK8") (pinfunction "LED_BUSY_AK8") (pintype "passive"))
    )
    (net (code "12") (name "/LED_BUSY4") (class "Default")
      (node (ref "D41") (pin "2") (pinfunction "A_2") (pintype "passive"))
      (node (ref "U4") (pin "AK8") (pinfunction "LED_BUSY_AK8") (pintype "passive"))
    )
    (net (code "13") (name "/LED_CLK1") (class "Default")
      (node (ref "D16") (pin "2") (pinfunction "A_2") (pintype "passive"))
      (node (ref "U13") (pin "AK5") (pinfunction "LED_CLK_AK5") (pintype "passive"))
    )
    (net (code "14") (name "/LED_CLK2") (class "Default")
      (node (ref "D29") (pin "2") (pinfunction "A_2") (pintype "passive"))
      (node (ref "U2") (pin "AK5") (pinfunction "LED_CLK_AK5") (pintype "passive"))
    )
    (net (code "15") (name "/LED_CLK3") (class "Default")
      (node (ref "D38") (pin "2") (pinfunction "A_2") (pintype "passive"))
      (node (ref "U3") (pin "AK5") (pinfunction "LED_CLK_AK5") (pintype "passive"))
    )
    (net (code "16") (name "/LED_CLK4") (class "Default")
      (node (ref "D45") (pin "2") (pinfunction "A_2") (pintype "passive"))
      (node (ref "U4") (pin "AK5") (pinfunction "LED_CLK_AK5") (pintype "passive"))
    )
    (net (code "17") (name "/LED_HOT1") (class "Default")
      (node (ref "D9") (pin "2") (pinfunction "A_2") (pintype "passive"))
      (node (ref "U13") (pin "AJ7") (pinfunction "LED_HOT_AJ7") (pintype "passive"))
    )
    (net (code "18") (name "/LED_HOT2") (class "Default")
      (node (ref "D27") (pin "2") (pinfunction "A_2") (pintype "passive"))
      (node (ref "U2") (pin "AJ7") (pinfunction "LED_HOT_AJ7") (pintype "passive"))
    )
    (net (code "19") (name "/LED_HOT3") (class "Default")
      (node (ref "D37") (pin "2") (pinfunction "A_2") (pintype "passive"))
      (node (ref "U3") (pin "AJ7") (pinfunction "LED_HOT_AJ7") (pintype "passive"))
    )
    (net (code "20") (name "/LED_HOT4") (class "Default")
      (node (ref "D44") (pin "2") (pinfunction "A_2") (pintype "passive"))
      (node (ref "U4") (pin "AJ7") (pinfunction "LED_HOT_AJ7") (pintype "passive"))
    )
    (net (code "21") (name "/LED_IDLE1") (class "Default")
      (node (ref "D5") (pin "2") (pinfunction "A_2") (pintype "passive"))
      (node (ref "U13") (pin "AJ8") (pinfunction "LED_IDLE_AJ8") (pintype "passive"))
    )
    (net (code "22") (name "/LED_IDLE2") (class "Default")
      (node (ref "D20") (pin "2") (pinfunction "A_2") (pintype "passive"))
      (node (ref "U2") (pin "AJ8") (pinfunction "LED_IDLE_AJ8") (pintype "passive"))
    )
    (net (code "23") (name "/LED_IDLE3") (class "Default")
      (node (ref "D33") (pin "2") (pinfunction "A_2") (pintype "passive"))
      (node (ref "U3") (pin "AJ8") (pinfunction "LED_IDLE_AJ8") (pintype "passive"))
    )
    (net (code "24") (name "/LED_IDLE4") (class "Default")
      (node (ref "D40") (pin "2") (pinfunction "A_2") (pintype "passive"))
      (node (ref "U4") (pin "AJ8") (pinfunction "LED_IDLE_AJ8") (pintype "passive"))
    )
    (net (code "25") (name "/LED_NONCE1") (class "Default")
      (node (ref "D17") (pin "2") (pinfunction "A_2") (pintype "passive"))
      (node (ref "U13") (pin "AK7") (pinfunction "LED_NONCE_AK7") (pintype "passive"))
    )
    (net (code "26") (name "/LED_NONCE2") (class "Default")
      (node (ref "D31") (pin "2") (pinfunction "A_2") (pintype "passive"))
      (node (ref "U2") (pin "AK7") (pinfunction "LED_NONCE_AK7") (pintype "passive"))
    )
    (net (code "27") (name "/LED_NONCE3") (class "Default")
      (node (ref "D39") (pin "2") (pinfunction "A_2") (pintype "passive"))
      (node (ref "U3") (pin "AK7") (pinfunction "LED_NONCE_AK7") (pintype "passive"))
    )
    (net (code "28") (name "/LED_NONCE4") (class "Default")
      (node (ref "D46") (pin "2") (pinfunction "A_2") (pintype "passive"))
      (node (ref "U4") (pin "AK7") (pinfunction "LED_NONCE_AK7") (pintype "passive"))
    )
    (net (code "29") (name "/LED_POWER1") (class "Default")
      (node (ref "D13") (pin "2") (pinfunction "A_2") (pintype "passive"))
      (node (ref "U13") (pin "AK9") (pinfunction "LED_POWER_AK9") (pintype "passive"))
    )
    (net (code "30") (name "/LED_POWER2") (class "Default")
      (node (ref "D25") (pin "2") (pinfunction "A_2") (pintype "passive"))
      (node (ref "U2") (pin "AK9") (pinfunction "LED_POWER_AK9") (pintype "passive"))
    )
    (net (code "31") (name "/LED_POWER3") (class "Default")
      (node (ref "D36") (pin "2") (pinfunction "A_2") (pintype "passive"))
      (node (ref "U3") (pin "AK9") (pinfunction "LED_POWER_AK9") (pintype "passive"))
    )
    (net (code "32") (name "/LED_POWER4") (class "Default")
      (node (ref "D43") (pin "2") (pinfunction "A_2") (pintype "passive"))
      (node (ref "U4") (pin "AK9") (pinfunction "LED_POWER_AK9") (pintype "passive"))
    )
    (net (code "33") (name "/LED_SPI1") (class "Default")
      (node (ref "D7") (pin "2") (pinfunction "A_2") (pintype "passive"))
      (node (ref "U13") (pin "AJ5") (pinfunction "LED_SPI_AJ5") (pintype "passive"))
    )
    (net (code "34") (name "/LED_SPI2") (class "Default")
      (node (ref "D24") (pin "2") (pinfunction "A_2") (pintype "passive"))
      (node (ref "U2") (pin "AJ5") (pinfunction "LED_SPI_AJ5") (pintype "passive"))
    )
    (net (code "35") (name "/LED_SPI3") (class "Default")
      (node (ref "D35") (pin "2") (pinfunction "A_2") (pintype "passive"))
      (node (ref "U3") (pin "AJ5") (pinfunction "LED_SPI_AJ5") (pintype "passive"))
    )
    (net (code "36") (name "/LED_SPI4") (class "Default")
      (node (ref "D42") (pin "2") (pinfunction "A_2") (pintype "passive"))
      (node (ref "U4") (pin "AJ5") (pinfunction "LED_SPI_AJ5") (pintype "passive"))
    )
    (net (code "37") (name "/POR_IOVSEL1") (class "Default")
      (node (ref "R19") (pin "2") (pinfunction "2_2") (pintype "passive"))
      (node (ref "U13") (pin "AJ13") (pinfunction "POR_IOVSEL_AJ13") (pintype "passive"))
    )
    (net (code "38") (name "/POR_IOVSEL2") (class "Default")
      (node (ref "R37") (pin "2") (pinfunction "2_2") (pintype "passive"))
      (node (ref "U2") (pin "AJ13") (pinfunction "POR_IOVSEL_AJ13") (pintype "passive"))
    )
    (net (code "39") (name "/POR_IOVSEL3") (class "Default")
      (node (ref "R39") (pin "2") (pinfunction "2_2") (pintype "passive"))
      (node (ref "U3") (pin "AJ13") (pinfunction "POR_IOVSEL_AJ13") (pintype "passive"))
    )
    (net (code "40") (name "/POR_IOVSEL4") (class "Default")
      (node (ref "R40") (pin "2") (pinfunction "2_2") (pintype "passive"))
      (node (ref "U4") (pin "AJ13") (pinfunction "POR_IOVSEL_AJ13") (pintype "passive"))
    )
    (net (code "41") (name "/RESET_ASIC") (class "Default")
      (node (ref "C594") (pin "1") (pinfunction "1_1") (pintype "passive"))
      (node (ref "C595") (pin "1") (pinfunction "1_1") (pintype "passive"))
      (node (ref "C597") (pin "1") (pinfunction "1_1") (pintype "passive"))
      (node (ref "C601") (pin "1") (pinfunction "1_1") (pintype "passive"))
      (node (ref "U13") (pin "AK28") (pinfunction "RSTN_IN_AK28") (pintype "passive"))
      (node (ref "U2") (pin "AK28") (pinfunction "RSTN_IN_AK28") (pintype "passive"))
      (node (ref "U3") (pin "AK28") (pinfunction "RSTN_IN_AK28") (pintype "passive"))
      (node (ref "U4") (pin "AK28") (pinfunction "RSTN_IN_AK28") (pintype "passive"))
    )
    (net (code "42") (name "/SPI_CS") (class "Default")
      (node (ref "U13") (pin "AJ25") (pinfunction "SPI_CSN_AJ25") (pintype "passive"))
      (node (ref "U2") (pin "AJ25") (pinfunction "SPI_CSN_AJ25") (pintype "passive"))
      (node (ref "U3") (pin "AJ25") (pinfunction "SPI_CSN_AJ25") (pintype "passive"))
      (node (ref "U4") (pin "AJ25") (pinfunction "SPI_CSN_AJ25") (pintype "passive"))
    )
    (net (code "43") (name "/SPI_MISO") (class "Default")
      (node (ref "U13") (pin "AJ24") (pinfunction "SPI_MISO_AJ24") (pintype "passive"))
      (node (ref "U2") (pin "AJ24") (pinfunction "SPI_MISO_AJ24") (pintype "passive"))
      (node (ref "U3") (pin "AJ24") (pinfunction "SPI_MISO_AJ24") (pintype "passive"))
      (node (ref "U4") (pin "AJ24") (pinfunction "SPI_MISO_AJ24") (pintype "passive"))
    )
    (net (code "44") (name "/SPI_MOSI") (class "Default")
      (node (ref "U13") (pin "AK25") (pinfunction "SPI_MOSI_AK25") (pintype "passive"))
      (node (ref "U2") (pin "AK25") (pinfunction "SPI_MOSI_AK25") (pintype "passive"))
      (node (ref "U3") (pin "AK25") (pinfunction "SPI_MOSI_AK25") (pintype "passive"))
      (node (ref "U4") (pin "AK25") (pinfunction "SPI_MOSI_AK25") (pintype "passive"))
    )
    (net (code "45") (name "/SPI_SCK") (class "Default")
      (node (ref "U13") (pin "AK27") (pinfunction "SPI_CLK_AK27") (pintype "passive"))
      (node (ref "U2") (pin "AK27") (pinfunction "SPI_CLK_AK27") (pintype "passive"))
      (node (ref "U3") (pin "AK27") (pinfunction "SPI_CLK_AK27") (pintype "passive"))
      (node (ref "U4") (pin "AK27") (pinfunction "SPI_CLK_AK27") (pintype "passive"))
    )
    (net (code "46") (name "/TEST_MODE1") (class "Default")
      (node (ref "R25") (pin "2") (pinfunction "2_2") (pintype "passive"))
      (node (ref "U13") (pin "AK3") (pinfunction "TEST_MODE_AK3") (pintype "passive"))
    )
    (net (code "47") (name "/TEST_MODE2") (class "Default")
      (node (ref "R38") (pin "2") (pinfunction "2_2") (pintype "passive"))
      (node (ref "U2") (pin "AK3") (pinfunction "TEST_MODE_AK3") (pintype "passive"))
    )
    (net (code "48") (name "/TEST_MODE3") (class "Default")
      (node (ref "R41") (pin "2") (pinfunction "2_2") (pintype "passive"))
      (node (ref "U3") (pin "AK3") (pinfunction "TEST_MODE_AK3") (pintype "passive"))
    )
    (net (code "49") (name "/TEST_MODE4") (class "Default")
      (node (ref "R42") (pin "2") (pinfunction "2_2") (pintype "passive"))
      (node (ref "U4") (pin "AK3") (pinfunction "TEST_MODE_AK3") (pintype "passive"))
    )
    (net (code "50") (name "/XCLK1") (class "Default")
      (node (ref "R1") (pin "1") (pinfunction "1_1") (pintype "passive"))
      (node (ref "U13") (pin "AK19") (pinfunction "XTAL12M_IN_AK19") (pintype "passive"))
      (node (ref "YO4") (pin "3") (pinfunction "OSC_3") (pintype "passive"))
      (node (ref "YO5") (pin "3") (pinfunction "OSC_3") (pintype "passive"))
      (node (ref "YO6") (pin "3") (pinfunction "OSC_3") (pintype "passive"))
      (node (ref "YO7") (pin "3") (pinfunction "OSC_3") (pintype "passive"))
    )
    (net (code "51") (name "/XCLK2") (class "Default")
      (node (ref "R1") (pin "2") (pinfunction "2_2") (pintype "passive"))
      (node (ref "R2") (pin "1") (pinfunction "1_1") (pintype "passive"))
      (node (ref "U2") (pin "AK19") (pinfunction "XTAL12M_IN_AK19") (pintype "passive"))
      (node (ref "YO1") (pin "3") (pinfunction "OSC_3") (pintype "passive"))
      (node (ref "YO2") (pin "3") (pinfunction "OSC_3") (pintype "passive"))
      (node (ref "YO3") (pin "3") (pinfunction "OSC_3") (pintype "passive"))
      (node (ref "YO8") (pin "3") (pinfunction "OSC_3") (pintype "passive"))
    )
    (net (code "52") (name "/XCLK3") (class "Default")
      (node (ref "R2") (pin "2") (pinfunction "2_2") (pintype "passive"))
      (node (ref "R3") (pin "1") (pinfunction "1_1") (pintype "passive"))
      (node (ref "U3") (pin "AK19") (pinfunction "XTAL12M_IN_AK19") (pintype "passive"))
      (node (ref "YO10") (pin "3") (pinfunction "OSC_3") (pintype "passive"))
      (node (ref "YO13") (pin "3") (pinfunction "OSC_3") (pintype "passive"))
      (node (ref "YO14") (pin "3") (pinfunction "OSC_3") (pintype "passive"))
      (node (ref "YO9") (pin "3") (pinfunction "OSC_3") (pintype "passive"))
    )
    (net (code "53") (name "/XCLK4") (class "Default")
      (node (ref "R3") (pin "2") (pinfunction "2_2") (pintype "passive"))
      (node (ref "U4") (pin "AK19") (pinfunction "XTAL12M_IN_AK19") (pintype "passive"))
      (node (ref "YO11") (pin "3") (pinfunction "OSC_3") (pintype "passive"))
      (node (ref "YO12") (pin "3") (pinfunction "OSC_3") (pintype "passive"))
      (node (ref "YO15") (pin "3") (pinfunction "OSC_3") (pintype "passive"))
      (node (ref "YO16") (pin "3") (pinfunction "OSC_3") (pintype "passive"))
    )
    (net (code "54") (name "/XCLK_OUT1") (class "Default")
      (node (ref "TP9") (pin "1") (pinfunction "1_1") (pintype "passive"))
      (node (ref "U13") (pin "AK18") (pinfunction "XTAL12M_OUT_AK18") (pintype "passive"))
    )
    (net (code "55") (name "/XCLK_OUT2") (class "Default")
      (node (ref "TP14") (pin "1") (pinfunction "1_1") (pintype "passive"))
      (node (ref "U2") (pin "AK18") (pinfunction "XTAL12M_OUT_AK18") (pintype "passive"))
    )
    (net (code "56") (name "/XCLK_OUT3") (class "Default")
      (node (ref "TP15") (pin "1") (pinfunction "1_1") (pintype "passive"))
      (node (ref "U3") (pin "AK18") (pinfunction "XTAL12M_OUT_AK18") (pintype "passive"))
    )
    (net (code "57") (name "/XCLK_OUT4") (class "Default")
      (node (ref "TP16") (pin "1") (pinfunction "1_1") (pintype "passive"))
      (node (ref "U4") (pin "AK18") (pinfunction "XTAL12M_OUT_AK18") (pintype "passive"))
    )
    (net (code "58") (name "GND") (class "Default")
      (node (ref "C106") (pin "1") (pinfunction "1_1") (pintype "passive"))
      (node (ref "C107") (pin "1") (pinfunction "1_1") (pintype "passive"))
      (node (ref "C108") (pin "1") (pinfunction "1_1") (pintype "passive"))
      (node (ref "C109") (pin "1") (pinfunction "1_1") (pintype "passive"))
      (node (ref "C110") (pin "1") (pinfunction "1_1") (pintype "passive"))
      (node (ref "C111") (pin "1") (pinfunction "1_1") (pintype "passive"))
      (node (ref "C112") (pin "1") (pinfunction "1_1") (pintype "passive"))
      (node (ref "C113") (pin "1") (pinfunction "1_1") (pintype "passive"))
      (node (ref "C114") (pin "1") (pinfunction "1_1") (pintype "passive"))
      (node (ref "C115") (pin "1") (pinfunction "1_1") (pintype "passive"))
      (node (ref "C118") (pin "1") (pinfunction "1_1") (pintype "passive"))
      (node (ref "C119") (pin "1") (pinfunction "1_1") (pintype "passive"))
      (node (ref "C122") (pin "1") (pinfunction "1_1") (pintype "passive"))
      (node (ref "C123") (pin "1") (pinfunction "1_1") (pintype "passive"))
      (node (ref "C126") (pin "1") (pinfunction "1_1") (pintype "passive"))
      (node (ref "C127") (pin "1") (pinfunction "1_1") (pintype "passive"))
      (node (ref "C138") (pin "1") (pinfunction "1_1") (pintype "passive"))
      (node (ref "C139") (pin "1") (pinfunction "1_1") (pintype "passive"))
      (node (ref "C140") (pin "1") (pinfunction "1_1") (pintype "passive"))
      (node (ref "C141") (pin "1") (pinfunction "1_1") (pintype "passive"))
      (node (ref "C142") (pin "1") (pinfunction "1_1") (pintype "passive"))
      (node (ref "C143") (pin "1") (pinfunction "1_1") (pintype "passive"))
      (node (ref "C144") (pin "1") (pinfunction "1_1") (pintype "passive"))
      (node (ref "C145") (pin "1") (pinfunction "1_1") (pintype "passive"))
      (node (ref "C146") (pin "1") (pinfunction "1_1") (pintype "passive"))
      (node (ref "C147") (pin "1") (pinfunction "1_1") (pintype "passive"))
      (node (ref "C148") (pin "1") (pinfunction "1_1") (pintype "passive"))
      (node (ref "C149") (pin "1") (pinfunction "1_1") (pintype "passive"))
      (node (ref "C150") (pin "1") (pinfunction "1_1") (pintype "passive"))
      (node (ref "C151") (pin "1") (pinfunction "1_1") (pintype "passive"))
      (node (ref "C152") (pin "1") (pinfunction "1_1") (pintype "passive"))
      (node (ref "C153") (pin "1") (pinfunction "1_1") (pintype "passive"))
      (node (ref "C154") (pin "1") (pinfunction "1_1") (pintype "passive"))
      (node (ref "C155") (pin "1") (pinfunction "1_1") (pintype "passive"))
      (node (ref "C156") (pin "1") (pinfunction "1_1") (pintype "passive"))
      (node (ref "C157") (pin "1") (pinfunction "1_1") (pintype "passive"))
      (node (ref "C158") (pin "1") (pinfunction "1_1") (pintype "passive"))
      (node (ref "C159") (pin "1") (pinfunction "1_1") (pintype "passive"))
      (node (ref "C160") (pin "1") (pinfunction "1_1") (pintype "passive"))
      (node (ref "C161") (pin "1") (pinfunction "1_1") (pintype "passive"))
      (node (ref "C162") (pin "1") (pinfunction "1_1") (pintype "passive"))
      (node (ref "C163") (pin "1") (pinfunction "1_1") (pintype "passive"))
      (node (ref "C164") (pin "1") (pinfunction "1_1") (pintype "passive"))
      (node (ref "C165") (pin "1") (pinfunction "1_1") (pintype "passive"))
      (node (ref "C166") (pin "1") (pinfunction "1_1") (pintype "passive"))
      (node (ref "C167") (pin "1") (pinfunction "1_1") (pintype "passive"))
      (node (ref "C169") (pin "1") (pinfunction "1_1") (pintype "passive"))
      (node (ref "C170") (pin "1") (pinfunction "1_1") (pintype "passive"))
      (node (ref "C171") (pin "1") (pinfunction "1_1") (pintype "passive"))
      (node (ref "C172") (pin "1") (pinfunction "1_1") (pintype "passive"))
      (node (ref "C173") (pin "1") (pinfunction "1_1") (pintype "passive"))
      (node (ref "C174") (pin "1") (pinfunction "1_1") (pintype "passive"))
      (node (ref "C175") (pin "1") (pinfunction "1_1") (pintype "passive"))
      (node (ref "C176") (pin "1") (pinfunction "1_1") (pintype "passive"))
      (node (ref "C177") (pin "1") (pinfunction "1_1") (pintype "passive"))
      (node (ref "C178") (pin "1") (pinfunction "1_1") (pintype "passive"))
      (node (ref "C179") (pin "1") (pinfunction "1_1") (pintype "passive"))
      (node (ref "C180") (pin "1") (pinfunction "1_1") (pintype "passive"))
      (node (ref "C19") (pin "1") (pinfunction "1_1") (pintype "passive"))
      (node (ref "C197") (pin "1") (pinfunction "1_1") (pintype "passive"))
      (node (ref "C198") (pin "1") (pinfunction "1_1") (pintype "passive"))
      (node (ref "C199") (pin "1") (pinfunction "1_1") (pintype "passive"))
      (node (ref "C200") (pin "1") (pinfunction "1_1") (pintype "passive"))
      (node (ref "C201") (pin "1") (pinfunction "1_1") (pintype "passive"))
      (node (ref "C202") (pin "1") (pinfunction "1_1") (pintype "passive"))
      (node (ref "C203") (pin "1") (pinfunction "1_1") (pintype "passive"))
      (node (ref "C204") (pin "1") (pinfunction "1_1") (pintype "passive"))
      (node (ref "C205") (pin "1") (pinfunction "1_1") (pintype "passive"))
      (node (ref "C206") (pin "1") (pinfunction "1_1") (pintype "passive"))
      (node (ref "C207") (pin "1") (pinfunction "1_1") (pintype "passive"))
      (node (ref "C208") (pin "1") (pinfunction "1_1") (pintype "passive"))
      (node (ref "C209") (pin "1") (pinfunction "1_1") (pintype "passive"))
      (node (ref "C210") (pin "1") (pinfunction "1_1") (pintype "passive"))
      (node (ref "C211") (pin "1") (pinfunction "1_1") (pintype "passive"))
      (node (ref "C212") (pin "1") (pinfunction "1_1") (pintype "passive"))
      (node (ref "C213") (pin "1") (pinfunction "1_1") (pintype "passive"))
      (node (ref "C214") (pin "1") (pinfunction "1_1") (pintype "passive"))
      (node (ref "C22") (pin "1") (pinfunction "1_1") (pintype "passive"))
      (node (ref "C23") (pin "1") (pinfunction "1_1") (pintype "passive"))
      (node (ref "C239") (pin "1") (pinfunction "1_1") (pintype "passive"))
      (node (ref "C26") (pin "1") (pinfunction "1_1") (pintype "passive"))
      (node (ref "C27") (pin "1") (pinfunction "1_1") (pintype "passive"))
      (node (ref "C289") (pin "1") (pinfunction "1_1") (pintype "passive"))
      (node (ref "C291") (pin "1") (pinfunction "1_1") (pintype "passive"))
      (node (ref "C293") (pin "1") (pinfunction "1_1") (pintype "passive"))
      (node (ref "C294") (pin "1") (pinfunction "1_1") (pintype "passive"))
      (node (ref "C30") (pin "1") (pinfunction "1_1") (pintype "passive"))
      (node (ref "C303") (pin "1") (pinfunction "1_1") (pintype "passive"))
      (node (ref "C304") (pin "1") (pinfunction "1_1") (pintype "passive"))
      (node (ref "C305") (pin "1") (pinfunction "1_1") (pintype "passive"))
      (node (ref "C306") (pin "1") (pinfunction "1_1") (pintype "passive"))
      (node (ref "C307") (pin "1") (pinfunction "1_1") (pintype "passive"))
      (node (ref "C309") (pin "1") (pinfunction "1_1") (pintype "passive"))
      (node (ref "C31") (pin "1") (pinfunction "1_1") (pintype "passive"))
      (node (ref "C315") (pin "1") (pinfunction "1_1") (pintype "passive"))
      (node (ref "C322") (pin "2") (pinfunction "2_2") (pintype "passive"))
      (node (ref "C36") (pin "1") (pinfunction "1_1") (pintype "passive"))
      (node (ref "C42") (pin "1") (pinfunction "1_1") (pintype "passive"))
      (node (ref "C43") (pin "1") (pinfunction "1_1") (pintype "passive"))
      (node (ref "C44") (pin "1") (pinfunction "1_1") (pintype "passive"))
      (node (ref "C45") (pin "1") (pinfunction "1_1") (pintype "passive"))
      (node (ref "C46") (pin "1") (pinfunction "1_1") (pintype "passive"))
      (node (ref "C47") (pin "1") (pinfunction "1_1") (pintype "passive"))
      (node (ref "C48") (pin "1") (pinfunction "1_1") (pintype "passive"))
      (node (ref "C49") (pin "1") (pinfunction "1_1") (pintype "passive"))
      (node (ref "C50") (pin "1") (pinfunction "1_1") (pintype "passive"))
      (node (ref "C51") (pin "1") (pinfunction "1_1") (pintype "passive"))
      (node (ref "C54") (pin "1") (pinfunction "1_1") (pintype "passive"))
      (node (ref "C55") (pin "1") (pinfunction "1_1") (pintype "passive"))
      (node (ref "C58") (pin "1") (pinfunction "1_1") (pintype "passive"))
      (node (ref "C59") (pin "1") (pinfunction "1_1") (pintype "passive"))
      (node (ref "C594") (pin "2") (pinfunction "2_2") (pintype "passive"))
      (node (ref "C595") (pin "2") (pinfunction "2_2") (pintype "passive"))
      (node (ref "C597") (pin "2") (pinfunction "2_2") (pintype "passive"))
      (node (ref "C601") (pin "2") (pinfunction "2_2") (pintype "passive"))
      (node (ref "C604") (pin "2") (pinfunction "2_2") (pintype "passive"))
      (node (ref "C609") (pin "2") (pinfunction "2_2") (pintype "passive"))
      (node (ref "C610") (pin "2") (pinfunction "2_2") (pintype "passive"))
      (node (ref "C616") (pin "1") (pinfunction "1_1") (pintype "passive"))
      (node (ref "C62") (pin "1") (pinfunction "1_1") (pintype "passive"))
      (node (ref "C63") (pin "1") (pinfunction "1_1") (pintype "passive"))
      (node (ref "C74") (pin "1") (pinfunction "1_1") (pintype "passive"))
      (node (ref "C75") (pin "1") (pinfunction "1_1") (pintype "passive"))
      (node (ref "C76") (pin "1") (pinfunction "1_1") (pintype "passive"))
      (node (ref "C77") (pin "1") (pinfunction "1_1") (pintype "passive"))
      (node (ref "C78") (pin "1") (pinfunction "1_1") (pintype "passive"))
      (node (ref "C79") (pin "1") (pinfunction "1_1") (pintype "passive"))
      (node (ref "C80") (pin "1") (pinfunction "1_1") (pintype "passive"))
      (node (ref "C81") (pin "1") (pinfunction "1_1") (pintype "passive"))
      (node (ref "C82") (pin "1") (pinfunction "1_1") (pintype "passive"))
      (node (ref "C83") (pin "1") (pinfunction "1_1") (pintype "passive"))
      (node (ref "C86") (pin "1") (pinfunction "1_1") (pintype "passive"))
      (node (ref "C87") (pin "1") (pinfunction "1_1") (pintype "passive"))
      (node (ref "C90") (pin "1") (pinfunction "1_1") (pintype "passive"))
      (node (ref "C91") (pin "1") (pinfunction "1_1") (pintype "passive"))
      (node (ref "C94") (pin "1") (pinfunction "1_1") (pintype "passive"))
      (node (ref "C95") (pin "1") (pinfunction "1_1") (pintype "passive"))
      (node (ref "D12") (pin "1") (pinfunction "C_1") (pintype "passive"))
      (node (ref "D13") (pin "1") (pinfunction "C_1") (pintype "passive"))
      (node (ref "D16") (pin "1") (pinfunction "C_1") (pintype "passive"))
      (node (ref "D17") (pin "1") (pinfunction "C_1") (pintype "passive"))
      (node (ref "D20") (pin "1") (pinfunction "C_1") (pintype "passive"))
      (node (ref "D21") (pin "1") (pinfunction "C_1") (pintype "passive"))
      (node (ref "D24") (pin "1") (pinfunction "C_1") (pintype "passive"))
      (node (ref "D25") (pin "1") (pinfunction "C_1") (pintype "passive"))
      (node (ref "D27") (pin "1") (pinfunction "C_1") (pintype "passive"))
      (node (ref "D29") (pin "1") (pinfunction "C_1") (pintype "passive"))
      (node (ref "D31") (pin "1") (pinfunction "C_1") (pintype "passive"))
      (node (ref "D33") (pin "1") (pinfunction "C_1") (pintype "passive"))
      (node (ref "D34") (pin "1") (pinfunction "C_1") (pintype "passive"))
      (node (ref "D35") (pin "1") (pinfunction "C_1") (pintype "passive"))
      (node (ref "D36") (pin "1") (pinfunction "C_1") (pintype "passive"))
      (node (ref "D37") (pin "1") (pinfunction "C_1") (pintype "passive"))
      (node (ref "D38") (pin "1") (pinfunction "C_1") (pintype "passive"))
      (node (ref "D39") (pin "1") (pinfunction "C_1") (pintype "passive"))
      (node (ref "D40") (pin "1") (pinfunction "C_1") (pintype "passive"))
      (node (ref "D41") (pin "1") (pinfunction "C_1") (pintype "passive"))
      (node (ref "D42") (pin "1") (pinfunction "C_1") (pintype "passive"))
      (node (ref "D43") (pin "1") (pinfunction "C_1") (pintype "passive"))
      (node (ref "D44") (pin "1") (pinfunction "C_1") (pintype "passive"))
      (node (ref "D45") (pin "1") (pinfunction "C_1") (pintype "passive"))
      (node (ref "D46") (pin "1") (pinfunction "C_1") (pintype "passive"))
      (node (ref "D5") (pin "1") (pinfunction "C_1") (pintype "passive"))
      (node (ref "D7") (pin "1") (pinfunction "C_1") (pintype "passive"))
      (node (ref "D9") (pin "1") (pinfunction "C_1") (pintype "passive"))
      (node (ref "R19") (pin "1") (pinfunction "1_1") (pintype "passive"))
      (node (ref "R25") (pin "1") (pinfunction "1_1") (pintype "passive"))
      (node (ref "R37") (pin "1") (pinfunction "1_1") (pintype "passive"))
      (node (ref "R38") (pin "1") (pinfunction "1_1") (pintype "passive"))
      (node (ref "R39") (pin "1") (pinfunction "1_1") (pintype "passive"))
      (node (ref "R40") (pin "1") (pinfunction "1_1") (pintype "passive"))
      (node (ref "R41") (pin "1") (pinfunction "1_1") (pintype "passive"))
      (node (ref "R42") (pin "1") (pinfunction "1_1") (pintype "passive"))
      (node (ref "U13") (pin "AJ20") (pinfunction "CHIP_ADDR0_AJ20") (pintype "passive"))
      (node (ref "U13") (pin "AJ21") (pinfunction "CHIP_ADDR2_AJ21") (pintype "passive"))
      (node (ref "U13") (pin "AJ22") (pinfunction "CHIP_ADDR4_AJ22") (pintype "passive"))
      (node (ref "U13") (pin "AJ26") (pinfunction "SPI_MODE_AJ26") (pintype "passive"))
      (node (ref "U13") (pin "AK11") (pinfunction "TSHUT_AGND18_AK11") (pintype "passive"))
      (node (ref "U13") (pin "AK12") (pinfunction "POR_AGND18_AK12") (pintype "passive"))
      (node (ref "U13") (pin "AK15") (pinfunction "PLL_AVSS_AK15") (pintype "passive"))
      (node (ref "U13") (pin "AK16") (pinfunction "PLL_AVSS2_AK16") (pintype "passive"))
      (node (ref "U13") (pin "AK21") (pinfunction "CHIP_ADDR1_AK21") (pintype "passive"))
      (node (ref "U13") (pin "AK22") (pinfunction "CHIP_ADDR3_AK22") (pintype "passive"))
      (node (ref "U2") (pin "AJ21") (pinfunction "CHIP_ADDR2_AJ21") (pintype "passive"))
      (node (ref "U2") (pin "AJ22") (pinfunction "CHIP_ADDR4_AJ22") (pintype "passive"))
      (node (ref "U2") (pin "AJ26") (pinfunction "SPI_MODE_AJ26") (pintype "passive"))
      (node (ref "U2") (pin "AK11") (pinfunction "TSHUT_AGND18_AK11") (pintype "passive"))
      (node (ref "U2") (pin "AK12") (pinfunction "POR_AGND18_AK12") (pintype "passive"))
      (node (ref "U2") (pin "AK15") (pinfunction "PLL_AVSS_AK15") (pintype "passive"))
      (node (ref "U2") (pin "AK16") (pinfunction "PLL_AVSS2_AK16") (pintype "passive"))
      (node (ref "U2") (pin "AK21") (pinfunction "CHIP_ADDR1_AK21") (pintype "passive"))
      (node (ref "U2") (pin "AK22") (pinfunction "CHIP_ADDR3_AK22") (pintype "passive"))
      (node (ref "U3") (pin "AJ20") (pinfunction "CHIP_ADDR0_AJ20") (pintype "passive"))
      (node (ref "U3") (pin "AJ21") (pinfunction "CHIP_ADDR2_AJ21") (pintype "passive"))
      (node (ref "U3") (pin "AJ22") (pinfunction "CHIP_ADDR4_AJ22") (pintype "passive"))
      (node (ref "U3") (pin "AJ26") (pinfunction "SPI_MODE_AJ26") (pintype "passive"))
      (node (ref "U3") (pin "AK11") (pinfunction "TSHUT_AGND18_AK11") (pintype "passive"))
      (node (ref "U3") (pin "AK12") (pinfunction "POR_AGND18_AK12") (pintype "passive"))
      (node (ref "U3") (pin "AK15") (pinfunction "PLL_AVSS_AK15") (pintype "passive"))
      (node (ref "U3") (pin "AK16") (pinfunction "PLL_AVSS2_AK16") (pintype "passive"))
      (node (ref "U3") (pin "AK22") (pinfunction "CHIP_ADDR3_AK22") (pintype "passive"))
      (node (ref "U4") (pin "AJ21") (pinfunction "CHIP_ADDR2_AJ21") (pintype "passive"))
      (node (ref "U4") (pin "AJ22") (pinfunction "CHIP_ADDR4_AJ22") (pintype "passive"))
      (node (ref "U4") (pin "AJ26") (pinfunction "SPI_MODE_AJ26") (pintype "passive"))
      (node (ref "U4") (pin "AK11") (pinfunction "TSHUT_AGND18_AK11") (pintype "passive"))
      (node (ref "U4") (pin "AK12") (pinfunction "POR_AGND18_AK12") (pintype "passive"))
      (node (ref "U4") (pin "AK15") (pinfunction "PLL_AVSS_AK15") (pintype "passive"))
      (node (ref "U4") (pin "AK16") (pinfunction "PLL_AVSS2_AK16") (pintype "passive"))
      (node (ref "U4") (pin "AK22") (pinfunction "CHIP_ADDR3_AK22") (pintype "passive"))
      (node (ref "YO1") (pin "2") (pinfunction "GND_2") (pintype "passive"))
      (node (ref "YO10") (pin "2") (pinfunction "GND_2") (pintype "passive"))
      (node (ref "YO11") (pin "2") (pinfunction "GND_2") (pintype "passive"))
      (node (ref "YO12") (pin "2") (pinfunction "GND_2") (pintype "passive"))
      (node (ref "YO13") (pin "2") (pinfunction "GND_2") (pintype "passive"))
      (node (ref "YO14") (pin "2") (pinfunction "GND_2") (pintype "passive"))
      (node (ref "YO15") (pin "2") (pinfunction "GND_2") (pintype "passive"))
      (node (ref "YO16") (pin "2") (pinfunction "GND_2") (pintype "passive"))
      (node (ref "YO2") (pin "2") (pinfunction "GND_2") (pintype "passive"))
      (node (ref "YO3") (pin "2") (pinfunction "GND_2") (pintype "passive"))
      (node (ref "YO4") (pin "2") (pinfunction "GND_2") (pintype "passive"))
      (node (ref "YO5") (pin "2") (pinfunction "GND_2") (pintype "passive"))
      (node (ref "YO6") (pin "2") (pinfunction "GND_2") (pintype "passive"))
      (node (ref "YO7") (pin "2") (pinfunction "GND_2") (pintype "passive"))
      (node (ref "YO8") (pin "2") (pinfunction "GND_2") (pintype "passive"))
      (node (ref "YO9") (pin "2") (pinfunction "GND_2") (pintype "passive"))
    )
  )
)
